# mainboard_rev_b.net
KiCad netlist of a schematic drawn in EAGLE
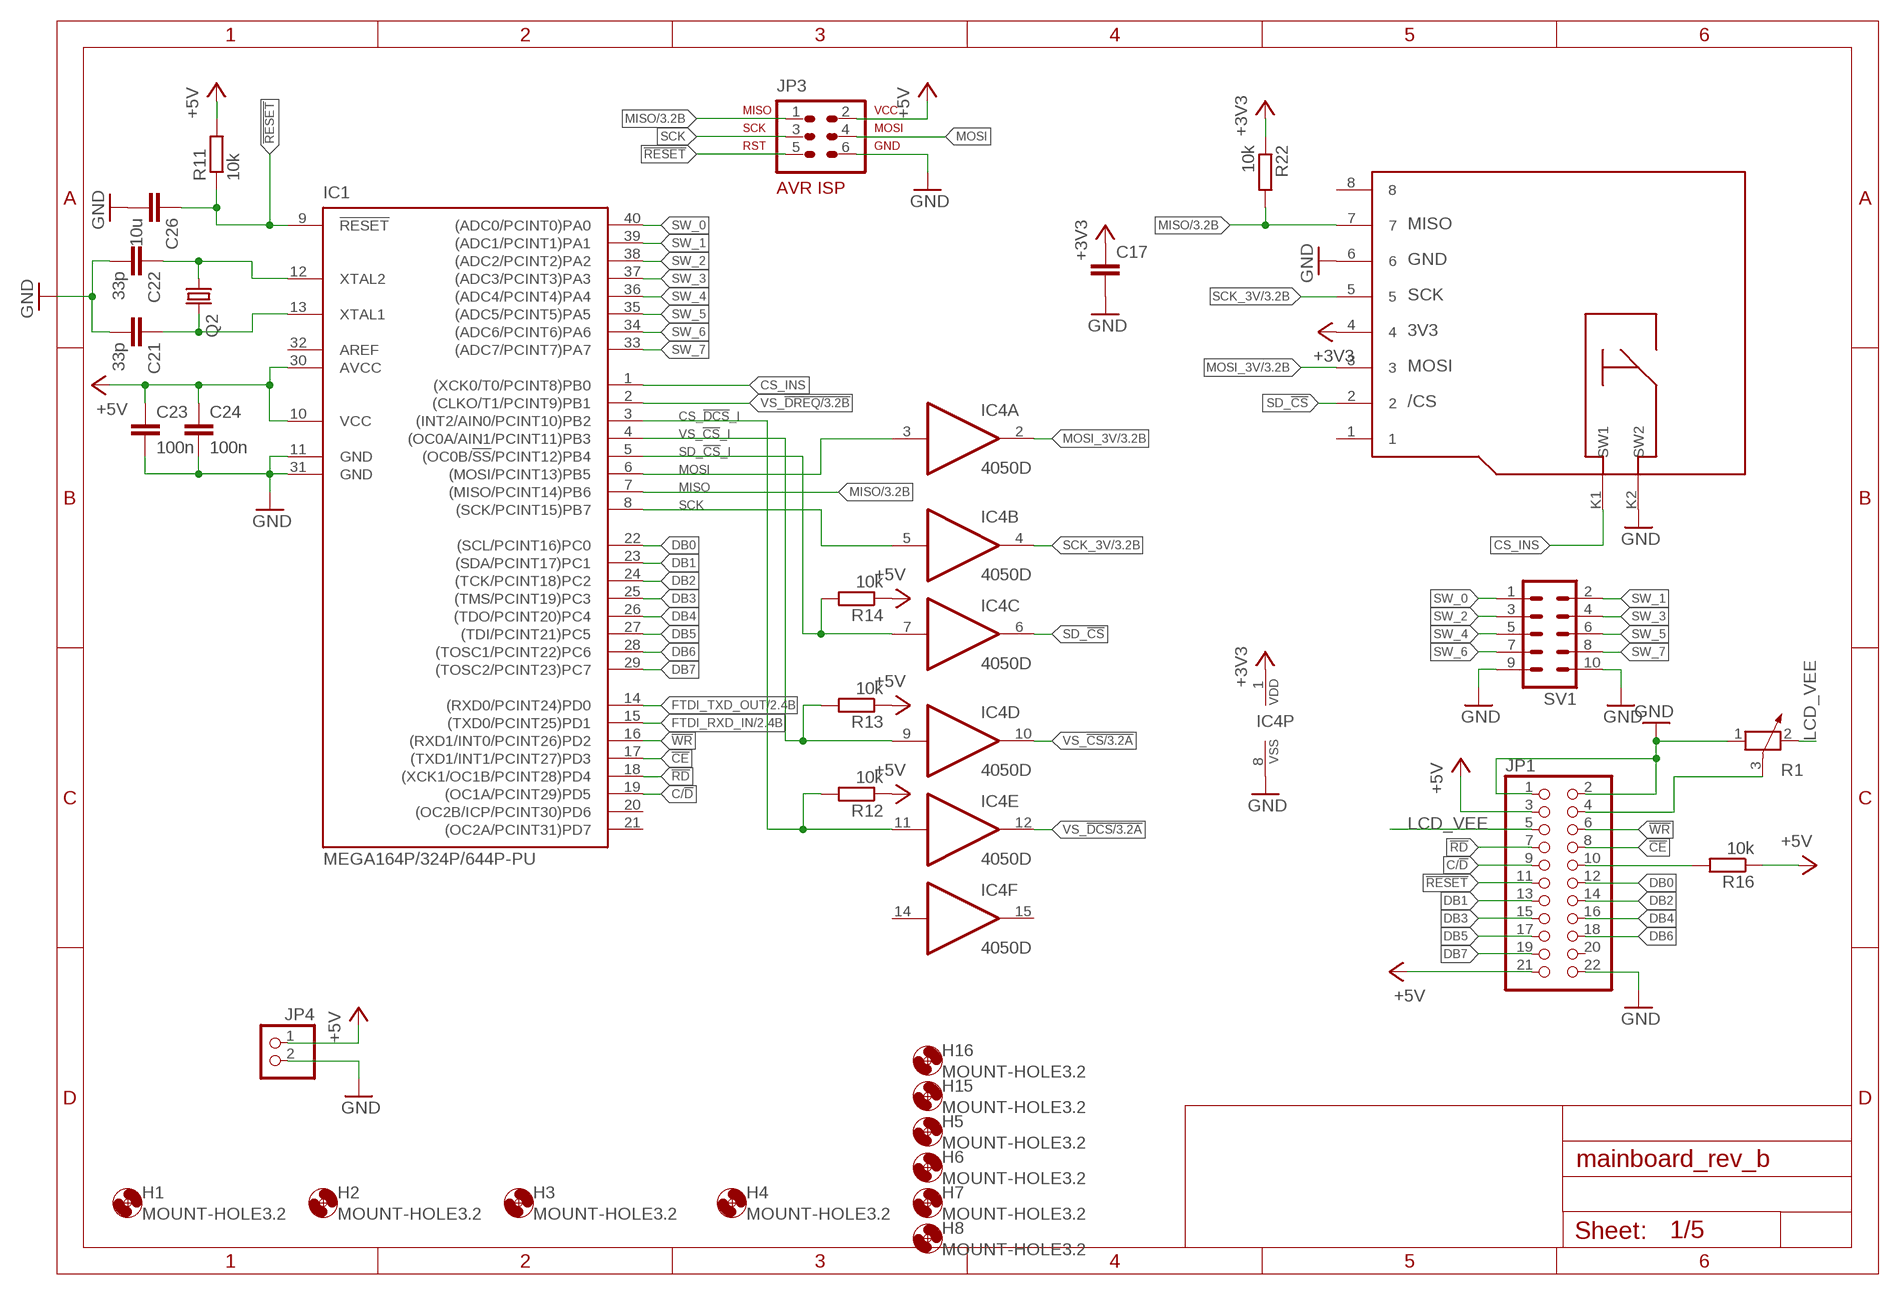
[diagram p0: schematic, sheet 1]
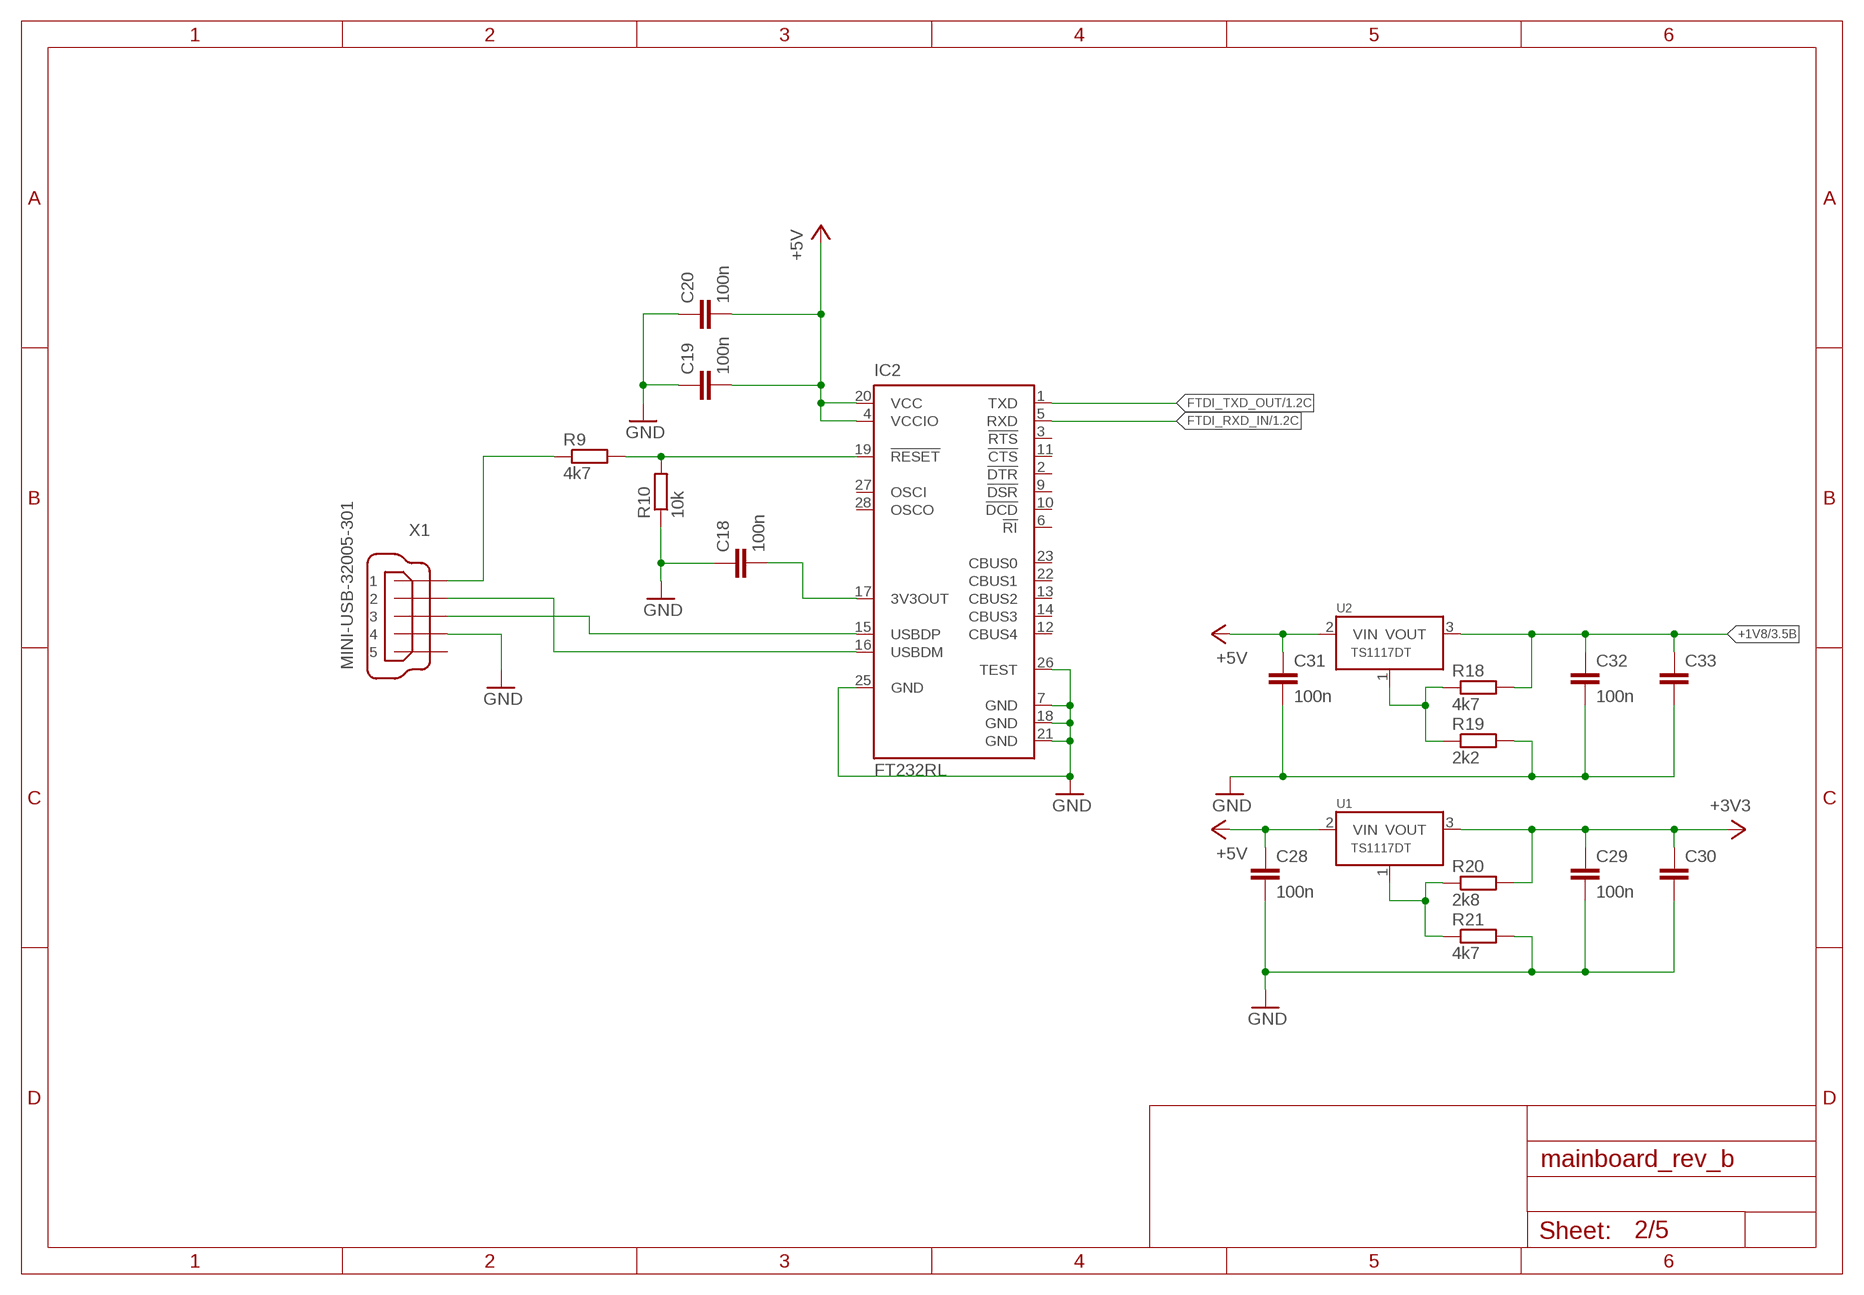
[diagram p1: schematic, sheet 2]
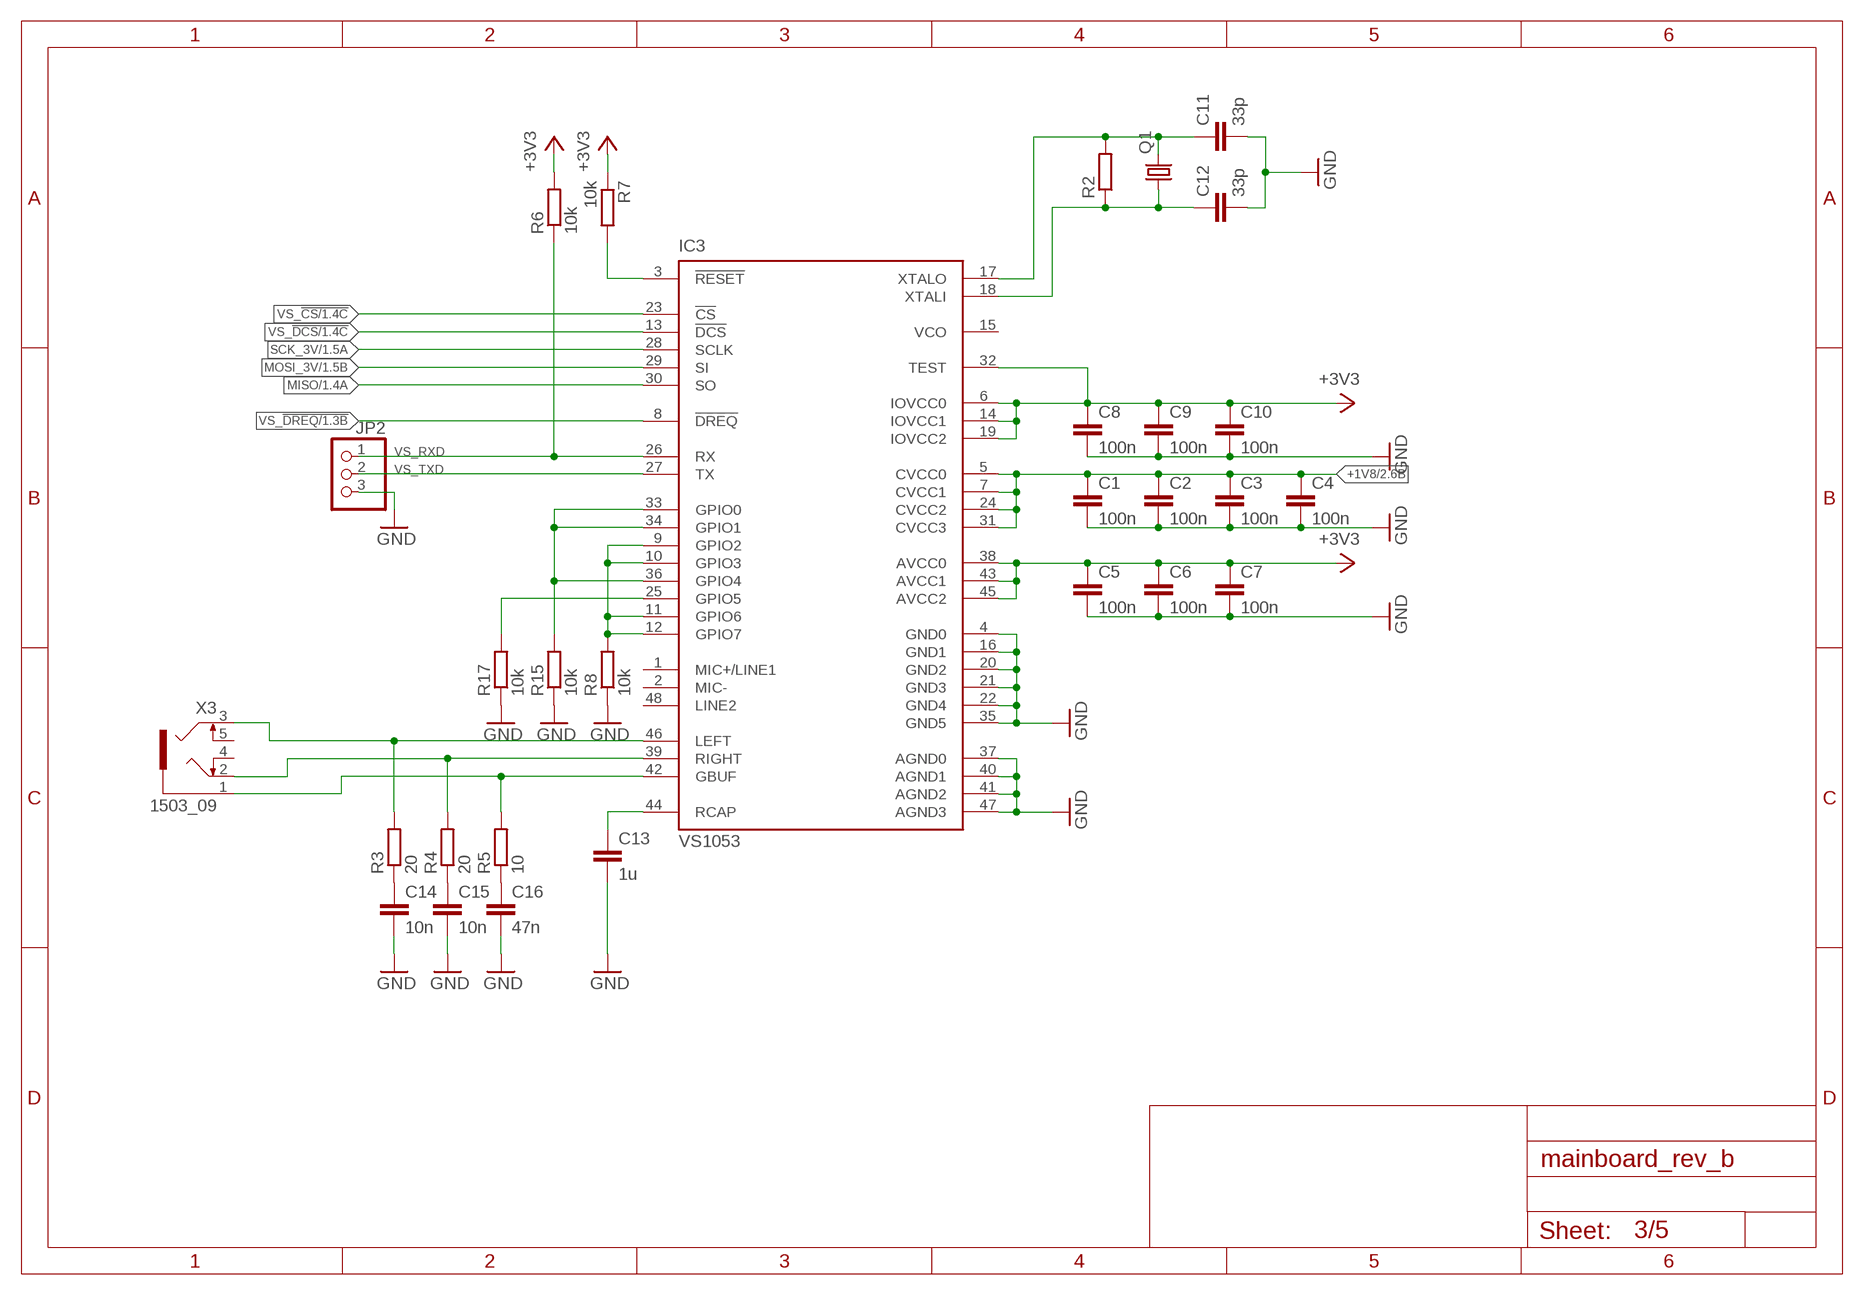
[diagram p2: schematic, sheet 3]
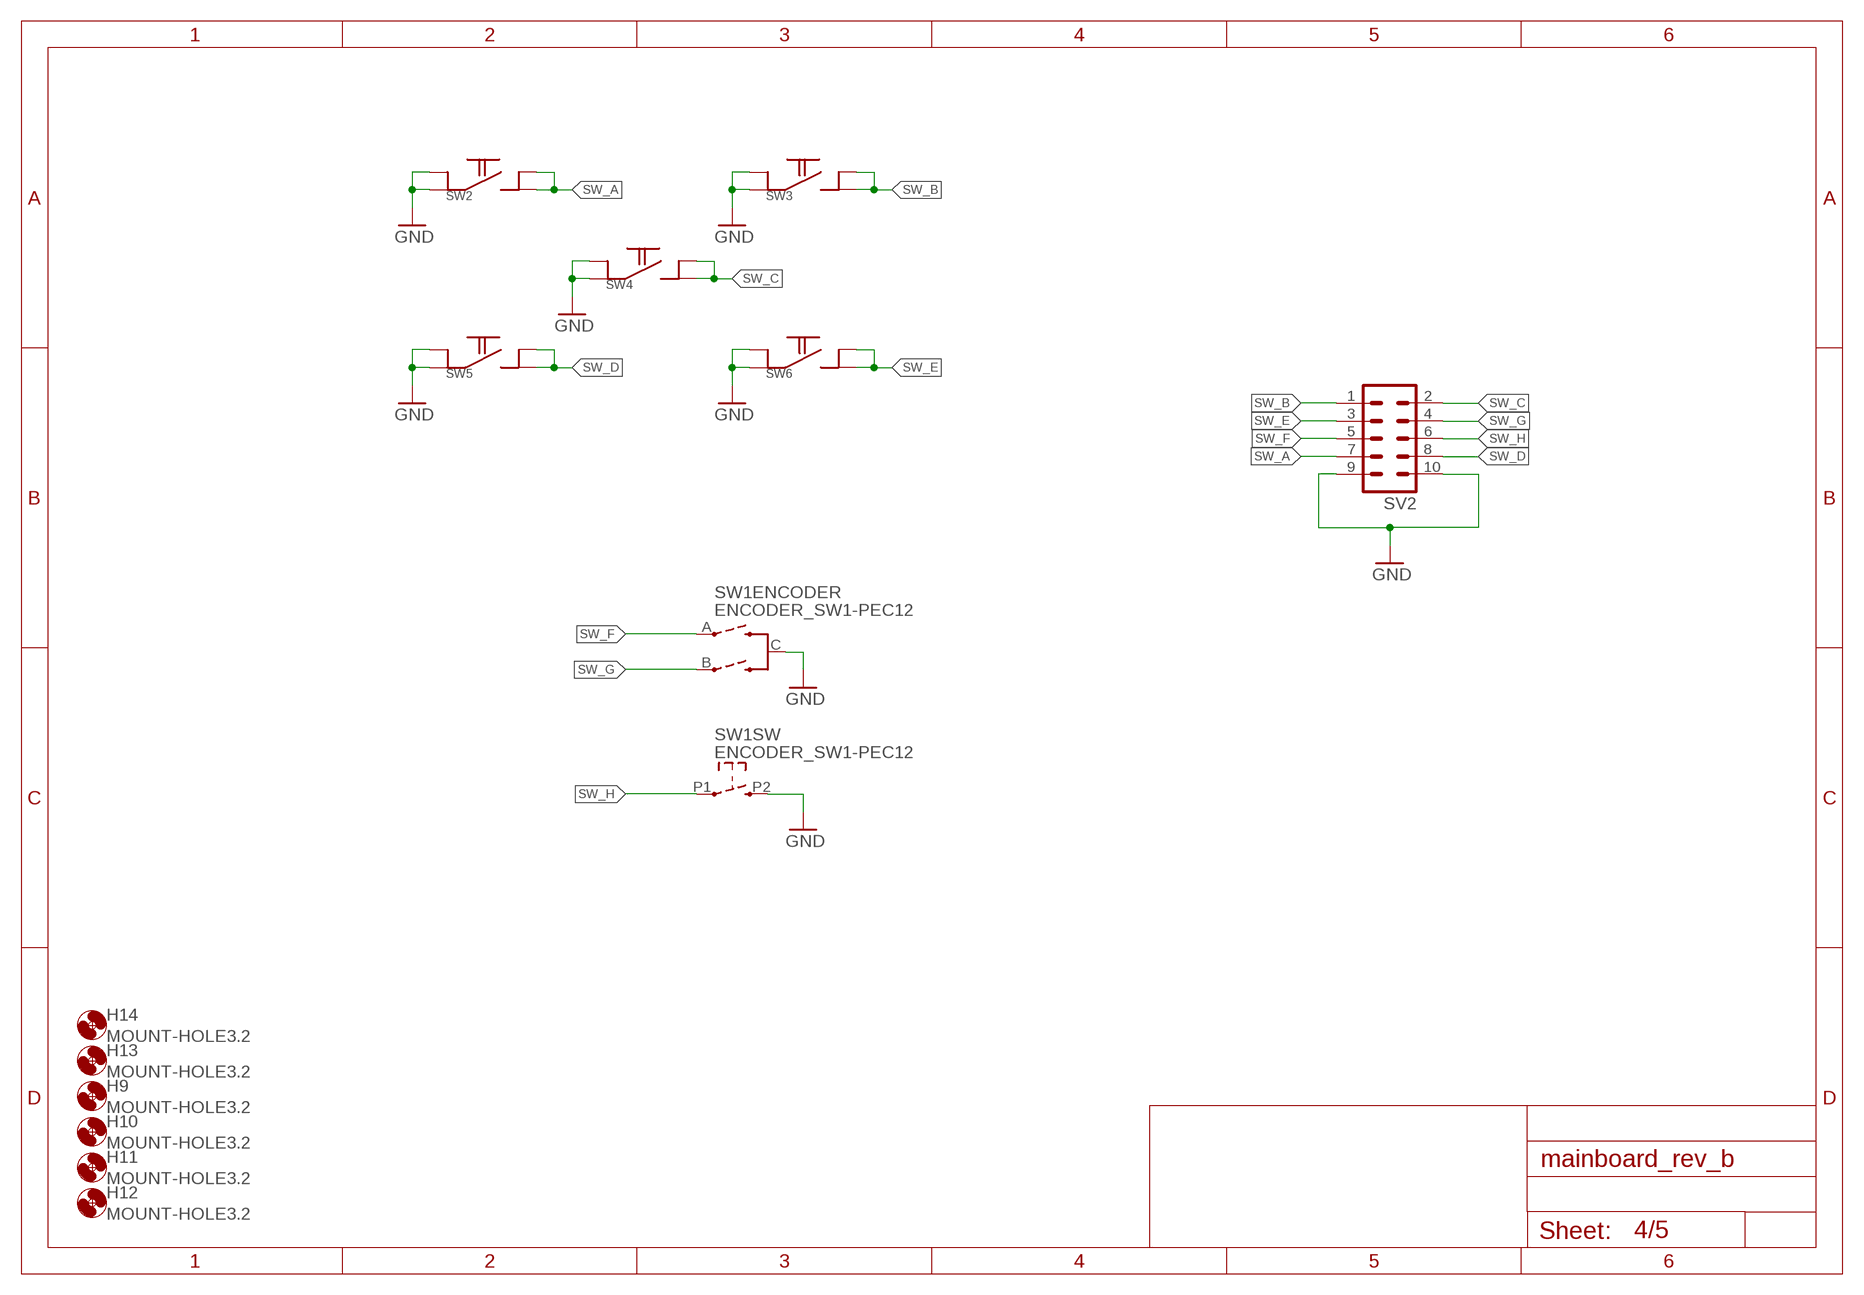
[diagram p3: schematic, sheet 4]
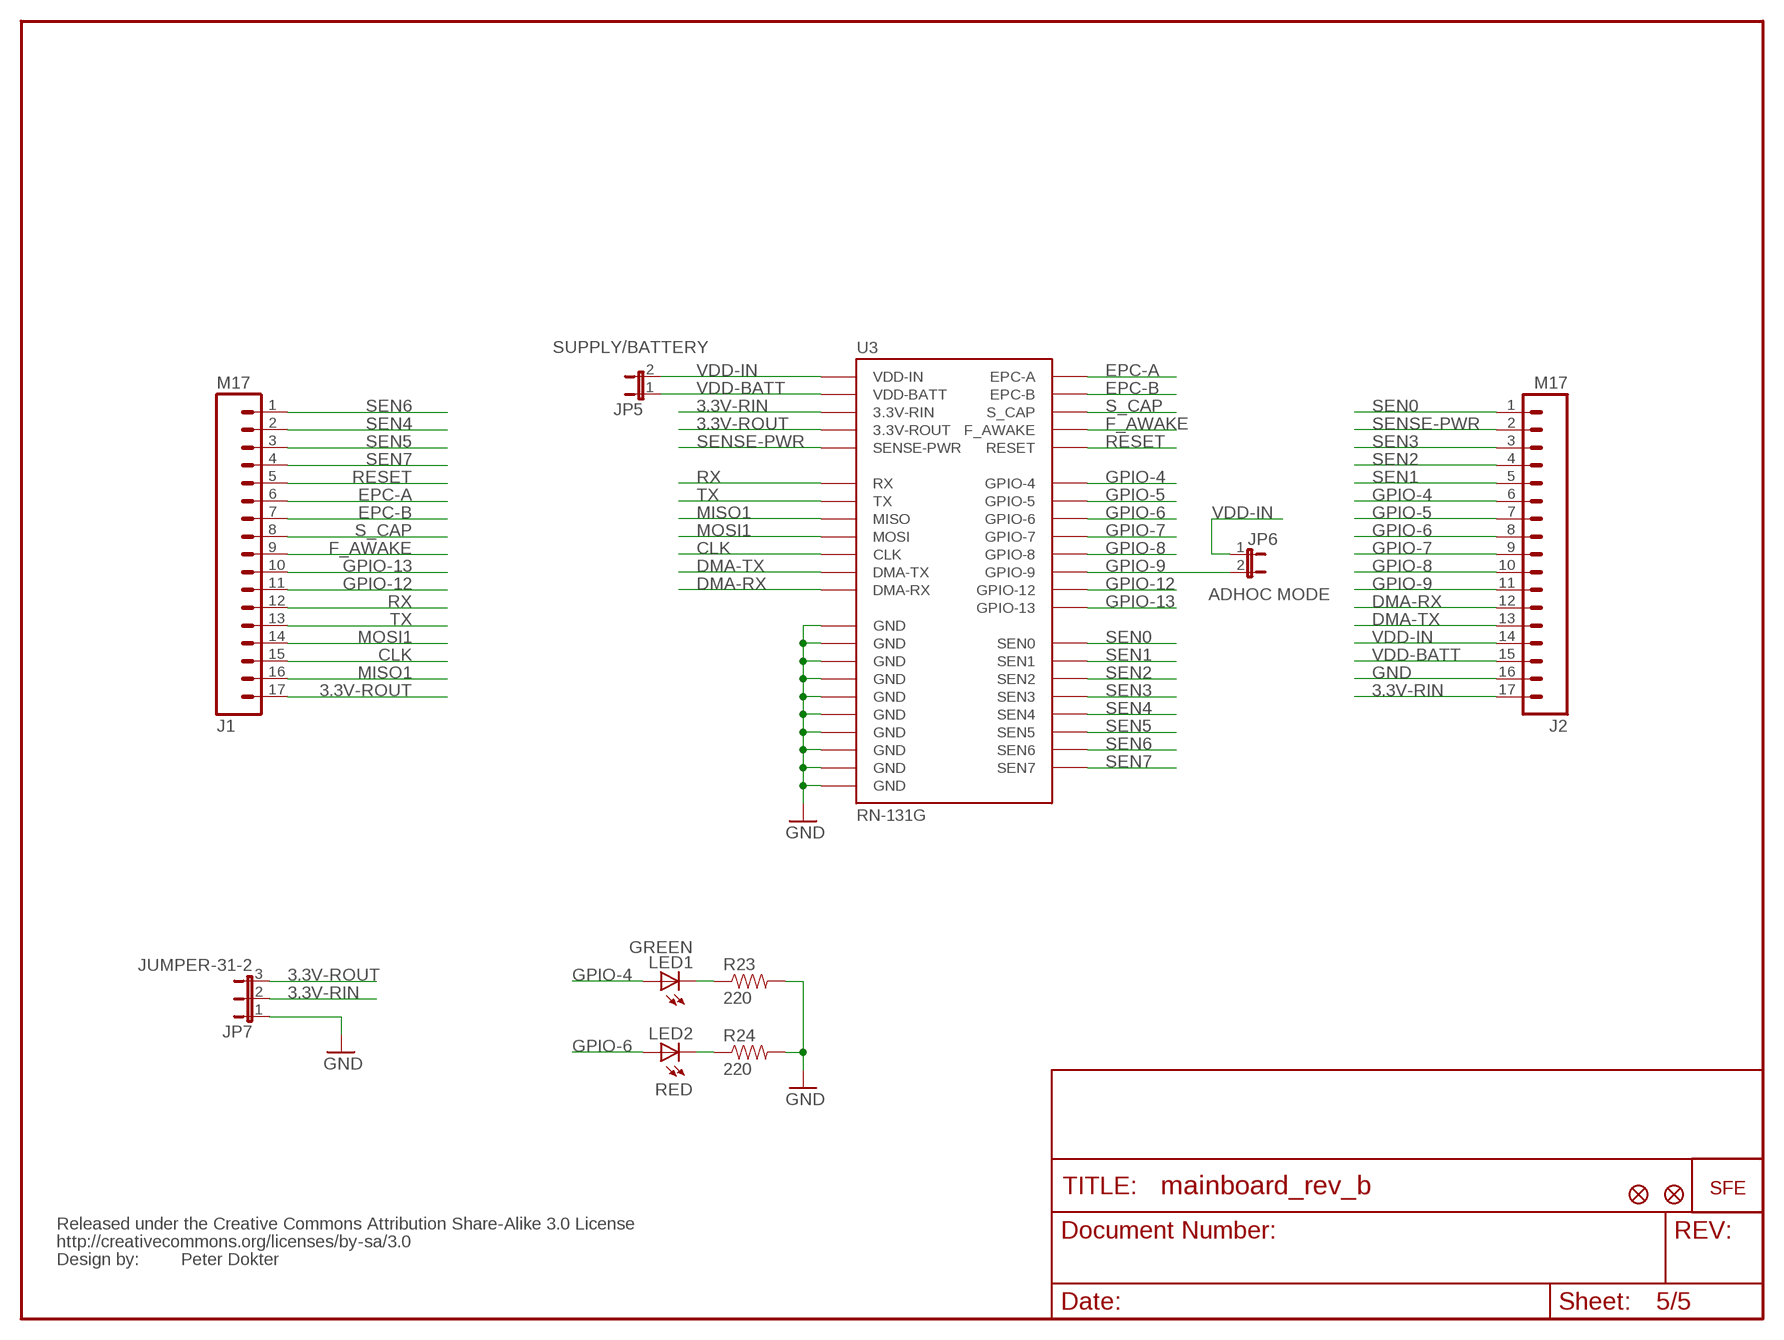
[diagram p4: schematic, sheet 5]

(export (version "E")
  (design (tool "Eeschema 10.0.6"))
  (components
    (comp (ref "H9")
      (value "MOUNT-HOLE3.2")
      (footprint "eagle-import:3,2")
      (libsource (lib "eagle-import") (part "MOUNT-HOLE3.2"))
    )
    (comp (ref "H10")
      (value "MOUNT-HOLE3.2")
      (footprint "eagle-import:3,2")
      (libsource (lib "eagle-import") (part "MOUNT-HOLE3.2"))
    )
    (comp (ref "H11")
      (value "MOUNT-HOLE3.2")
      (footprint "eagle-import:3,2")
      (libsource (lib "eagle-import") (part "MOUNT-HOLE3.2"))
    )
    (comp (ref "H12")
      (value "MOUNT-HOLE3.2")
      (footprint "eagle-import:3,2")
      (libsource (lib "eagle-import") (part "MOUNT-HOLE3.2"))
    )
    (comp (ref "H13")
      (value "MOUNT-HOLE3.2")
      (footprint "eagle-import:3,2")
      (libsource (lib "eagle-import") (part "MOUNT-HOLE3.2"))
    )
    (comp (ref "H14")
      (value "MOUNT-HOLE3.2")
      (footprint "eagle-import:3,2")
      (libsource (lib "eagle-import") (part "MOUNT-HOLE3.2"))
    )
    (comp (ref "SV2")
      (value "ML10")
      (footprint "eagle-import:ML10")
      (libsource (lib "eagle-import") (part "ML10"))
    )
    (comp (ref "SW1")
      (value "ENCODER_SW1-PEC12")
      (footprint "eagle-import:PEC12_INCREMENTAL_ENCODER")
      (libsource (lib "eagle-import") (part "ENCODER_SW1-PEC12"))
    )
    (comp (ref "SW2")
      (value "PUSHBUTTON_12X12")
      (footprint "eagle-import:PUSHBUTTON_12X12")
      (libsource (lib "eagle-import") (part "PUSHBUTTON_12X12"))
    )
    (comp (ref "SW3")
      (value "PUSHBUTTON_12X12")
      (footprint "eagle-import:PUSHBUTTON_12X12")
      (libsource (lib "eagle-import") (part "PUSHBUTTON_12X12"))
    )
    (comp (ref "SW4")
      (value "PUSHBUTTON_12X12")
      (footprint "eagle-import:PUSHBUTTON_12X12")
      (libsource (lib "eagle-import") (part "PUSHBUTTON_12X12"))
    )
    (comp (ref "SW5")
      (value "PUSHBUTTON_12X12")
      (footprint "eagle-import:PUSHBUTTON_12X12")
      (libsource (lib "eagle-import") (part "PUSHBUTTON_12X12"))
    )
    (comp (ref "SW6")
      (value "PUSHBUTTON_12X12")
      (footprint "eagle-import:PUSHBUTTON_12X12")
      (libsource (lib "eagle-import") (part "PUSHBUTTON_12X12"))
    )
    (comp (ref "C1")
      (value "100n")
      (footprint "eagle-import:C0603")
      (libsource (lib "eagle-import") (part "C-EUC0603"))
    )
    (comp (ref "C2")
      (value "100n")
      (footprint "eagle-import:C0603")
      (libsource (lib "eagle-import") (part "C-EUC0603"))
    )
    (comp (ref "C3")
      (value "100n")
      (footprint "eagle-import:C0603")
      (libsource (lib "eagle-import") (part "C-EUC0603"))
    )
    (comp (ref "C4")
      (value "100n")
      (footprint "eagle-import:C0603")
      (libsource (lib "eagle-import") (part "C-EUC0603"))
    )
    (comp (ref "C5")
      (value "100n")
      (footprint "eagle-import:C0603")
      (libsource (lib "eagle-import") (part "C-EUC0603"))
    )
    (comp (ref "C6")
      (value "100n")
      (footprint "eagle-import:C0603")
      (libsource (lib "eagle-import") (part "C-EUC0603"))
    )
    (comp (ref "C7")
      (value "100n")
      (footprint "eagle-import:C0603")
      (libsource (lib "eagle-import") (part "C-EUC0603"))
    )
    (comp (ref "C8")
      (value "100n")
      (footprint "eagle-import:C0603")
      (libsource (lib "eagle-import") (part "C-EUC0603"))
    )
    (comp (ref "C9")
      (value "100n")
      (footprint "eagle-import:C0603")
      (libsource (lib "eagle-import") (part "C-EUC0603"))
    )
    (comp (ref "C10")
      (value "100n")
      (footprint "eagle-import:C0603")
      (libsource (lib "eagle-import") (part "C-EUC0603"))
    )
    (comp (ref "C11")
      (value "33p")
      (footprint "eagle-import:C0603")
      (libsource (lib "eagle-import") (part "C-EUC0603"))
    )
    (comp (ref "C12")
      (value "33p")
      (footprint "eagle-import:C0603")
      (libsource (lib "eagle-import") (part "C-EUC0603"))
    )
    (comp (ref "C13")
      (value "1u")
      (footprint "eagle-import:C0805")
      (libsource (lib "eagle-import") (part "C-EUC0805"))
    )
    (comp (ref "C14")
      (value "10n")
      (footprint "eagle-import:C0603")
      (libsource (lib "eagle-import") (part "C-EUC0603"))
    )
    (comp (ref "C15")
      (value "10n")
      (footprint "eagle-import:C0603")
      (libsource (lib "eagle-import") (part "C-EUC0603"))
    )
    (comp (ref "C16")
      (value "47n")
      (footprint "eagle-import:C0603")
      (libsource (lib "eagle-import") (part "C-EUC0603"))
    )
    (comp (ref "IC3")
      (value "VS1053")
      (footprint "eagle-import:LQFP-48")
      (libsource (lib "eagle-import") (part "VS1053"))
    )
    (comp (ref "JP2")
      (value "PINHD-1X3")
      (footprint "eagle-import:1X03")
      (libsource (lib "eagle-import") (part "PINHD-1X3"))
    )
    (comp (ref "Q1")
      (value "CRYSTALHC49UP")
      (footprint "eagle-import:HC49UP")
      (libsource (lib "eagle-import") (part "CRYSTALHC49UP"))
    )
    (comp (ref "R2")
      (value "R-EU_R0603")
      (footprint "eagle-import:R0603")
      (libsource (lib "eagle-import") (part "R-EU_R0603"))
    )
    (comp (ref "R3")
      (value "20")
      (footprint "eagle-import:R0603")
      (libsource (lib "eagle-import") (part "R-EU_R0603"))
    )
    (comp (ref "R4")
      (value "20")
      (footprint "eagle-import:R0603")
      (libsource (lib "eagle-import") (part "R-EU_R0603"))
    )
    (comp (ref "R5")
      (value "10")
      (footprint "eagle-import:R0603")
      (libsource (lib "eagle-import") (part "R-EU_R0603"))
    )
    (comp (ref "R6")
      (value "10k")
      (footprint "eagle-import:R0603")
      (libsource (lib "eagle-import") (part "R-EU_R0603"))
    )
    (comp (ref "R7")
      (value "10k")
      (footprint "eagle-import:R0603")
      (libsource (lib "eagle-import") (part "R-EU_R0603"))
    )
    (comp (ref "R8")
      (value "10k")
      (footprint "eagle-import:R0603")
      (libsource (lib "eagle-import") (part "R-EU_R0603"))
    )
    (comp (ref "R15")
      (value "10k")
      (footprint "eagle-import:R0603")
      (libsource (lib "eagle-import") (part "R-EU_R0603"))
    )
    (comp (ref "R17")
      (value "10k")
      (footprint "eagle-import:R0603")
      (libsource (lib "eagle-import") (part "R-EU_R0603"))
    )
    (comp (ref "X3")
      (value "1503_09")
      (footprint "eagle-import:1503_09")
      (libsource (lib "eagle-import") (part "1503_09"))
    )
    (comp (ref "J1")
      (value "M17")
      (footprint "eagle-import:1X17")
      (libsource (lib "eagle-import") (part "M17"))
    )
    (comp (ref "J2")
      (value "M17")
      (footprint "eagle-import:1X17")
      (libsource (lib "eagle-import") (part "M17"))
    )
    (comp (ref "JP5")
      (value "JUMPER-2SMD-NO")
      (footprint "eagle-import:SJ_2S-NO")
      (libsource (lib "eagle-import") (part "JUMPER-2SMD-NO"))
    )
    (comp (ref "JP6")
      (value "JUMPER-2SMD-NO")
      (footprint "eagle-import:SJ_2S-NO")
      (libsource (lib "eagle-import") (part "JUMPER-2SMD-NO"))
    )
    (comp (ref "JP7")
      (value "JUMPER-31-2")
      (footprint "eagle-import:SJ_3_PASTE1&2")
      (libsource (lib "eagle-import") (part "JUMPER-31-2"))
    )
    (comp (ref "LED1")
      (value "GREEN")
      (footprint "eagle-import:LED-0603")
      (libsource (lib "eagle-import") (part "LED0603"))
    )
    (comp (ref "LED2")
      (value "RED")
      (footprint "eagle-import:LED-0603")
      (libsource (lib "eagle-import") (part "LED0603"))
    )
    (comp (ref "R23")
      (value "220")
      (footprint "eagle-import:0402-RES")
      (libsource (lib "eagle-import") (part "RESISTOR0402-RES"))
    )
    (comp (ref "R24")
      (value "220")
      (footprint "eagle-import:0402-RES")
      (libsource (lib "eagle-import") (part "RESISTOR0402-RES"))
    )
    (comp (ref "U$1")
      (value "LOGO-SFENEW")
      (footprint "eagle-import:SFE-NEW-WEBLOGO")
      (libsource (lib "eagle-import") (part "LOGO-SFENEW"))
    )
    (comp (ref "U$2")
      (value "FIDUCIAL1X2")
      (footprint "eagle-import:FIDUCIAL-1X2")
      (libsource (lib "eagle-import") (part "FIDUCIAL1X2"))
    )
    (comp (ref "U$3")
      (value "FIDUCIAL1X2")
      (footprint "eagle-import:FIDUCIAL-1X2")
      (libsource (lib "eagle-import") (part "FIDUCIAL1X2"))
    )
    (comp (ref "U$4")
      (value "CREATIVE_COMMONS")
      (footprint "eagle-import:CREATIVE_COMMONS")
      (libsource (lib "eagle-import") (part "CREATIVE_COMMONS"))
    )
    (comp (ref "U3")
      (value "RN-131G")
      (footprint "eagle-import:RN-131G")
      (libsource (lib "eagle-import") (part "RN-131G"))
    )
    (comp (ref "C18")
      (value "100n")
      (footprint "eagle-import:C0603")
      (libsource (lib "eagle-import") (part "C-EUC0603"))
    )
    (comp (ref "C19")
      (value "100n")
      (footprint "eagle-import:C0603")
      (libsource (lib "eagle-import") (part "C-EUC0603"))
    )
    (comp (ref "C20")
      (value "100n")
      (footprint "eagle-import:C0603")
      (libsource (lib "eagle-import") (part "C-EUC0603"))
    )
    (comp (ref "C28")
      (value "100n")
      (footprint "eagle-import:C0603")
      (libsource (lib "eagle-import") (part "C-EUC0603"))
    )
    (comp (ref "C29")
      (value "100n")
      (footprint "eagle-import:C0603")
      (libsource (lib "eagle-import") (part "C-EUC0603"))
    )
    (comp (ref "C30")
      (value "C-EUC1206")
      (footprint "eagle-import:C1206")
      (libsource (lib "eagle-import") (part "C-EUC1206"))
    )
    (comp (ref "C31")
      (value "100n")
      (footprint "eagle-import:C0603")
      (libsource (lib "eagle-import") (part "C-EUC0603"))
    )
    (comp (ref "C32")
      (value "100n")
      (footprint "eagle-import:C0603")
      (libsource (lib "eagle-import") (part "C-EUC0603"))
    )
    (comp (ref "C33")
      (value "C-EUC1206")
      (footprint "eagle-import:C1206")
      (libsource (lib "eagle-import") (part "C-EUC1206"))
    )
    (comp (ref "IC2")
      (value "FT232RL")
      (footprint "eagle-import:SSOP28")
      (libsource (lib "eagle-import") (part "FT232RL"))
    )
    (comp (ref "R9")
      (value "4k7")
      (footprint "eagle-import:R0603")
      (libsource (lib "eagle-import") (part "R-EU_R0603"))
    )
    (comp (ref "R10")
      (value "10k")
      (footprint "eagle-import:R0603")
      (libsource (lib "eagle-import") (part "R-EU_R0603"))
    )
    (comp (ref "R18")
      (value "4k7")
      (footprint "eagle-import:R0603")
      (libsource (lib "eagle-import") (part "R-EU_R0603"))
    )
    (comp (ref "R19")
      (value "2k2")
      (footprint "eagle-import:R0603")
      (libsource (lib "eagle-import") (part "R-EU_R0603"))
    )
    (comp (ref "R20")
      (value "2k8")
      (footprint "eagle-import:R0603")
      (libsource (lib "eagle-import") (part "R-EU_R0603"))
    )
    (comp (ref "R21")
      (value "4k7")
      (footprint "eagle-import:R0603")
      (libsource (lib "eagle-import") (part "R-EU_R0603"))
    )
    (comp (ref "U1")
      (value "TS1117DT")
      (footprint "eagle-import:TO252")
      (libsource (lib "eagle-import") (part "TS1117DT"))
    )
    (comp (ref "U2")
      (value "TS1117DT")
      (footprint "eagle-import:TO252")
      (libsource (lib "eagle-import") (part "TS1117DT"))
    )
    (comp (ref "X1")
      (value "MINI-USB-32005-301")
      (footprint "eagle-import:32005-301")
      (libsource (lib "eagle-import") (part "MINI-USB-32005-301"))
    )
    (comp (ref "C17")
      (value "C-EUC1206")
      (footprint "eagle-import:C1206")
      (libsource (lib "eagle-import") (part "C-EUC1206"))
    )
    (comp (ref "C21")
      (value "33p")
      (footprint "eagle-import:C0603")
      (libsource (lib "eagle-import") (part "C-EUC0603"))
    )
    (comp (ref "C22")
      (value "33p")
      (footprint "eagle-import:C0603")
      (libsource (lib "eagle-import") (part "C-EUC0603"))
    )
    (comp (ref "C23")
      (value "100n")
      (footprint "eagle-import:C0603")
      (libsource (lib "eagle-import") (part "C-EUC0603"))
    )
    (comp (ref "C24")
      (value "100n")
      (footprint "eagle-import:C0603")
      (libsource (lib "eagle-import") (part "C-EUC0603"))
    )
    (comp (ref "C26")
      (value "10u")
      (footprint "eagle-import:C1206")
      (libsource (lib "eagle-import") (part "C-EUC1206"))
    )
    (comp (ref "H1")
      (value "MOUNT-HOLE3.2")
      (footprint "eagle-import:3,2")
      (libsource (lib "eagle-import") (part "MOUNT-HOLE3.2"))
    )
    (comp (ref "H2")
      (value "MOUNT-HOLE3.2")
      (footprint "eagle-import:3,2")
      (libsource (lib "eagle-import") (part "MOUNT-HOLE3.2"))
    )
    (comp (ref "H3")
      (value "MOUNT-HOLE3.2")
      (footprint "eagle-import:3,2")
      (libsource (lib "eagle-import") (part "MOUNT-HOLE3.2"))
    )
    (comp (ref "H4")
      (value "MOUNT-HOLE3.2")
      (footprint "eagle-import:3,2")
      (libsource (lib "eagle-import") (part "MOUNT-HOLE3.2"))
    )
    (comp (ref "H5")
      (value "MOUNT-HOLE3.2")
      (footprint "eagle-import:3,2")
      (libsource (lib "eagle-import") (part "MOUNT-HOLE3.2"))
    )
    (comp (ref "H6")
      (value "MOUNT-HOLE3.2")
      (footprint "eagle-import:3,2")
      (libsource (lib "eagle-import") (part "MOUNT-HOLE3.2"))
    )
    (comp (ref "H7")
      (value "MOUNT-HOLE3.2")
      (footprint "eagle-import:3,2")
      (libsource (lib "eagle-import") (part "MOUNT-HOLE3.2"))
    )
    (comp (ref "H8")
      (value "MOUNT-HOLE3.2")
      (footprint "eagle-import:3,2")
      (libsource (lib "eagle-import") (part "MOUNT-HOLE3.2"))
    )
    (comp (ref "H15")
      (value "MOUNT-HOLE3.2")
      (footprint "eagle-import:3,2")
      (libsource (lib "eagle-import") (part "MOUNT-HOLE3.2"))
    )
    (comp (ref "H16")
      (value "MOUNT-HOLE3.2")
      (footprint "eagle-import:3,2")
      (libsource (lib "eagle-import") (part "MOUNT-HOLE3.2"))
    )
    (comp (ref "IC1")
      (value "MEGA164P/324P/644P-PU")
      (footprint "eagle-import:DIL40")
      (libsource (lib "eagle-import") (part "MEGA164P/324P/644P-PU"))
    )
    (comp (ref "IC4")
      (value "4050D")
      (footprint "eagle-import:SO16")
      (libsource (lib "eagle-import") (part "4050D"))
    )
    (comp (ref "JP1")
      (value "PINHD-2X11")
      (footprint "eagle-import:2X11")
      (libsource (lib "eagle-import") (part "PINHD-2X11"))
    )
    (comp (ref "JP3")
      (value "AVR-ISP-6VERT")
      (footprint "eagle-import:AVR-ISP-6")
      (libsource (lib "eagle-import") (part "AVR-ISP-6VERT"))
    )
    (comp (ref "JP4")
      (value "PINHD-1X2")
      (footprint "eagle-import:1X02")
      (libsource (lib "eagle-import") (part "PINHD-1X2"))
    )
    (comp (ref "Q2")
      (value "CRYSTALHC49UP")
      (footprint "eagle-import:HC49UP")
      (libsource (lib "eagle-import") (part "CRYSTALHC49UP"))
    )
    (comp (ref "R1")
      (value "POTENTIOMETER_PT_SPIN")
      (footprint "eagle-import:PT-SPIN")
      (libsource (lib "eagle-import") (part "POTENTIOMETER_PT_SPIN"))
    )
    (comp (ref "R11")
      (value "10k")
      (footprint "eagle-import:R0603")
      (libsource (lib "eagle-import") (part "R-EU_R0603"))
    )
    (comp (ref "R12")
      (value "10k")
      (footprint "eagle-import:R0603")
      (libsource (lib "eagle-import") (part "R-EU_R0603"))
    )
    (comp (ref "R13")
      (value "10k")
      (footprint "eagle-import:R0603")
      (libsource (lib "eagle-import") (part "R-EU_R0603"))
    )
    (comp (ref "R14")
      (value "10k")
      (footprint "eagle-import:R0603")
      (libsource (lib "eagle-import") (part "R-EU_R0603"))
    )
    (comp (ref "R16")
      (value "10k")
      (footprint "eagle-import:R0603")
      (libsource (lib "eagle-import") (part "R-EU_R0603"))
    )
    (comp (ref "R22")
      (value "10k")
      (footprint "eagle-import:R0603")
      (libsource (lib "eagle-import") (part "R-EU_R0603"))
    )
    (comp (ref "SV1")
      (value "ML10")
      (footprint "eagle-import:ML10")
      (libsource (lib "eagle-import") (part "ML10"))
    )
    (comp (ref "X2")
      (value "MICRO-SD")
      (footprint "eagle-import:MICRO-SD")
      (libsource (lib "eagle-import") (part "MICRO-SD"))
    )
  )
  (nets
    (net (code "1") (name "+1V8") (class "Default")
      (node (ref "C1") (pin "1") (pinfunction "1_1") (pintype "passive"))
      (node (ref "C2") (pin "1") (pinfunction "1_1") (pintype "passive"))
      (node (ref "C3") (pin "1") (pinfunction "1_1") (pintype "passive"))
      (node (ref "C32") (pin "1") (pinfunction "1_1") (pintype "passive"))
      (node (ref "C33") (pin "1") (pinfunction "1_1") (pintype "passive"))
      (node (ref "C4") (pin "1") (pinfunction "1_1") (pintype "passive"))
      (node (ref "IC3") (pin "24") (pinfunction "CVCC2_24") (pintype "power_in"))
      (node (ref "IC3") (pin "31") (pinfunction "CVCC3_31") (pintype "power_in"))
      (node (ref "IC3") (pin "5") (pinfunction "CVCC0_5") (pintype "power_in"))
      (node (ref "IC3") (pin "7") (pinfunction "CVCC1_7") (pintype "power_in"))
      (node (ref "R18") (pin "2") (pinfunction "2_2") (pintype "passive"))
      (node (ref "U2") (pin "3") (pinfunction "VOUT_3") (pintype "power_in"))
    )
    (net (code "2") (name "+3V3") (class "Default")
      (node (ref "C10") (pin "1") (pinfunction "1_1") (pintype "passive"))
      (node (ref "C17") (pin "1") (pinfunction "1_1") (pintype "passive"))
      (node (ref "C29") (pin "1") (pinfunction "1_1") (pintype "passive"))
      (node (ref "C30") (pin "1") (pinfunction "1_1") (pintype "passive"))
      (node (ref "C5") (pin "1") (pinfunction "1_1") (pintype "passive"))
      (node (ref "C6") (pin "1") (pinfunction "1_1") (pintype "passive"))
      (node (ref "C7") (pin "1") (pinfunction "1_1") (pintype "passive"))
      (node (ref "C8") (pin "1") (pinfunction "1_1") (pintype "passive"))
      (node (ref "C9") (pin "1") (pinfunction "1_1") (pintype "passive"))
      (node (ref "IC3") (pin "14") (pinfunction "IOVCC1_14") (pintype "power_in"))
      (node (ref "IC3") (pin "19") (pinfunction "IOVCC2_19") (pintype "power_in"))
      (node (ref "IC3") (pin "32") (pinfunction "TEST_32") (pintype "input"))
      (node (ref "IC3") (pin "38") (pinfunction "AVCC0_38") (pintype "power_in"))
      (node (ref "IC3") (pin "43") (pinfunction "AVCC1_43") (pintype "power_in"))
      (node (ref "IC3") (pin "45") (pinfunction "AVCC2_45") (pintype "power_in"))
      (node (ref "IC3") (pin "6") (pinfunction "IOVCC0_6") (pintype "power_in"))
      (node (ref "IC4") (pin "1") (pinfunction "VDD_1") (pintype "power_in"))
      (node (ref "R20") (pin "2") (pinfunction "2_2") (pintype "passive"))
      (node (ref "R22") (pin "1") (pinfunction "1_1") (pintype "passive"))
      (node (ref "R6") (pin "2") (pinfunction "2_2") (pintype "passive"))
      (node (ref "R7") (pin "1") (pinfunction "1_1") (pintype "passive"))
      (node (ref "U1") (pin "3") (pinfunction "VOUT_3") (pintype "power_in"))
      (node (ref "X2") (pin "4") (pinfunction "4_4") (pintype "bidirectional"))
    )
    (net (code "3") (name "+5V") (class "Default")
      (node (ref "C19") (pin "2") (pinfunction "2_2") (pintype "passive"))
      (node (ref "C20") (pin "2") (pinfunction "2_2") (pintype "passive"))
      (node (ref "C23") (pin "1") (pinfunction "1_1") (pintype "passive"))
      (node (ref "C24") (pin "1") (pinfunction "1_1") (pintype "passive"))
      (node (ref "C28") (pin "1") (pinfunction "1_1") (pintype "passive"))
      (node (ref "C31") (pin "1") (pinfunction "1_1") (pintype "passive"))
      (node (ref "IC1") (pin "10") (pinfunction "VCC_10") (pintype "power_in"))
      (node (ref "IC1") (pin "30") (pinfunction "AVCC_30") (pintype "power_in"))
      (node (ref "IC2") (pin "20") (pinfunction "VCC_20") (pintype "power_in"))
      (node (ref "IC2") (pin "4") (pinfunction "VCCIO_4") (pintype "power_in"))
      (node (ref "JP1") (pin "21") (pinfunction "21_21") (pintype "passive"))
      (node (ref "JP1") (pin "3") (pinfunction "3_3") (pintype "passive"))
      (node (ref "JP3") (pin "2") (pinfunction "2_2") (pintype "passive"))
      (node (ref "JP4") (pin "1") (pinfunction "1_1") (pintype "passive"))
      (node (ref "R11") (pin "2") (pinfunction "2_2") (pintype "passive"))
      (node (ref "R12") (pin "1") (pinfunction "1_1") (pintype "passive"))
      (node (ref "R13") (pin "1") (pinfunction "1_1") (pintype "passive"))
      (node (ref "R14") (pin "1") (pinfunction "1_1") (pintype "passive"))
      (node (ref "R16") (pin "1") (pinfunction "1_1") (pintype "passive"))
      (node (ref "U1") (pin "2") (pinfunction "VIN_2") (pintype "power_in"))
      (node (ref "U2") (pin "2") (pinfunction "VIN_2") (pintype "power_in"))
    )
    (net (code "4") (name "3.3V-RIN") (class "Default")
      (node (ref "J2") (pin "17") (pinfunction "17_17") (pintype "passive"))
      (node (ref "JP7") (pin "2") (pinfunction "2_2") (pintype "passive"))
      (node (ref "U3") (pin "P$18") (pinfunction "3.3V-RIN_P$18") (pintype "bidirectional"))
    )
    (net (code "5") (name "3.3V-ROUT") (class "Default")
      (node (ref "J1") (pin "17") (pinfunction "17_17") (pintype "passive"))
      (node (ref "JP7") (pin "3") (pinfunction "3_3") (pintype "passive"))
      (node (ref "U3") (pin "P$17") (pinfunction "3.3V-ROUT_P$17") (pintype "bidirectional"))
    )
    (net (code "6") (name "AREF") (class "Default")
      (node (ref "IC1") (pin "32") (pinfunction "AREF_32") (pintype "power_in"))
    )
    (net (code "7") (name "CLK") (class "Default")
      (node (ref "J1") (pin "15") (pinfunction "15_15") (pintype "passive"))
      (node (ref "U3") (pin "P$15") (pinfunction "CLK_P$15") (pintype "bidirectional"))
    )
    (net (code "8") (name "CS_INS") (class "Default")
      (node (ref "IC1") (pin "1") (pinfunction "(XCK0/T0/PCINT8)PB0_1") (pintype "bidirectional"))
      (node (ref "X2") (pin "K1") (pinfunction "SW1_K1") (pintype "bidirectional"))
    )
    (net (code "9") (name "CS_~{DCS}_I") (class "Default")
      (node (ref "IC1") (pin "3") (pinfunction "(INT2/AIN0/PCINT10)PB2_3") (pintype "bidirectional"))
      (node (ref "IC4") (pin "11") (pinfunction "I_11") (pintype "input"))
      (node (ref "R12") (pin "2") (pinfunction "2_2") (pintype "passive"))
    )
    (net (code "10") (name "C{slash}~{D}") (class "Default")
      (node (ref "IC1") (pin "19") (pinfunction "(OC1A/PCINT29)PD5_19") (pintype "bidirectional"))
      (node (ref "JP1") (pin "9") (pinfunction "9_9") (pintype "passive"))
    )
    (net (code "11") (name "DB0") (class "Default")
      (node (ref "IC1") (pin "22") (pinfunction "(SCL/PCINT16)PC0_22") (pintype "bidirectional"))
      (node (ref "JP1") (pin "12") (pinfunction "12_12") (pintype "passive"))
    )
    (net (code "12") (name "DB1") (class "Default")
      (node (ref "IC1") (pin "23") (pinfunction "(SDA/PCINT17)PC1_23") (pintype "bidirectional"))
      (node (ref "JP1") (pin "13") (pinfunction "13_13") (pintype "passive"))
    )
    (net (code "13") (name "DB2") (class "Default")
      (node (ref "IC1") (pin "24") (pinfunction "(TCK/PCINT18)PC2_24") (pintype "bidirectional"))
      (node (ref "JP1") (pin "14") (pinfunction "14_14") (pintype "passive"))
    )
    (net (code "14") (name "DB3") (class "Default")
      (node (ref "IC1") (pin "25") (pinfunction "(TMS/PCINT19)PC3_25") (pintype "bidirectional"))
      (node (ref "JP1") (pin "15") (pinfunction "15_15") (pintype "passive"))
    )
    (net (code "15") (name "DB4") (class "Default")
      (node (ref "IC1") (pin "26") (pinfunction "(TDO/PCINT20)PC4_26") (pintype "bidirectional"))
      (node (ref "JP1") (pin "16") (pinfunction "16_16") (pintype "passive"))
    )
    (net (code "16") (name "DB5") (class "Default")
      (node (ref "IC1") (pin "27") (pinfunction "(TDI/PCINT21)PC5_27") (pintype "bidirectional"))
      (node (ref "JP1") (pin "17") (pinfunction "17_17") (pintype "passive"))
    )
    (net (code "17") (name "DB6") (class "Default")
      (node (ref "IC1") (pin "28") (pinfunction "(TOSC1/PCINT22)PC6_28") (pintype "bidirectional"))
      (node (ref "JP1") (pin "18") (pinfunction "18_18") (pintype "passive"))
    )
    (net (code "18") (name "DB7") (class "Default")
      (node (ref "IC1") (pin "29") (pinfunction "(TOSC2/PCINT23)PC7_29") (pintype "bidirectional"))
      (node (ref "JP1") (pin "19") (pinfunction "19_19") (pintype "passive"))
    )
    (net (code "19") (name "DMA-RX") (class "Default")
      (node (ref "J2") (pin "12") (pinfunction "12_12") (pintype "passive"))
      (node (ref "U3") (pin "P$23") (pinfunction "DMA-RX_P$23") (pintype "bidirectional"))
    )
    (net (code "20") (name "DMA-TX") (class "Default")
      (node (ref "J2") (pin "13") (pinfunction "13_13") (pintype "passive"))
      (node (ref "U3") (pin "P$22") (pinfunction "DMA-TX_P$22") (pintype "bidirectional"))
    )
    (net (code "21") (name "EPC-A") (class "Default")
      (node (ref "J1") (pin "6") (pinfunction "6_6") (pintype "passive"))
      (node (ref "U3") (pin "P$6") (pinfunction "EPC-A_P$6") (pintype "bidirectional"))
    )
    (net (code "22") (name "EPC-B") (class "Default")
      (node (ref "J1") (pin "7") (pinfunction "7_7") (pintype "passive"))
      (node (ref "U3") (pin "P$7") (pinfunction "EPC-B_P$7") (pintype "bidirectional"))
    )
    (net (code "23") (name "FTDI_RXD_IN") (class "Default")
      (node (ref "IC1") (pin "15") (pinfunction "(TXD0/PCINT25)PD1_15") (pintype "bidirectional"))
      (node (ref "IC2") (pin "5") (pinfunction "RXD_5") (pintype "input"))
    )
    (net (code "24") (name "FTDI_TXD_OUT") (class "Default")
      (node (ref "IC1") (pin "14") (pinfunction "(RXD0/PCINT24)PD0_14") (pintype "bidirectional"))
      (node (ref "IC2") (pin "1") (pinfunction "TXD_1") (pintype "output"))
    )
    (net (code "25") (name "F_AWAKE") (class "Default")
      (node (ref "J1") (pin "9") (pinfunction "9_9") (pintype "passive"))
      (node (ref "U3") (pin "P$9") (pinfunction "F_AWAKE_P$9") (pintype "bidirectional"))
    )
    (net (code "26") (name "GND") (class "Default")
      (node (ref "C1") (pin "2") (pinfunction "2_2") (pintype "passive"))
      (node (ref "C10") (pin "2") (pinfunction "2_2") (pintype "passive"))
      (node (ref "C11") (pin "2") (pinfunction "2_2") (pintype "passive"))
      (node (ref "C12") (pin "2") (pinfunction "2_2") (pintype "passive"))
      (node (ref "C13") (pin "2") (pinfunction "2_2") (pintype "passive"))
      (node (ref "C14") (pin "2") (pinfunction "2_2") (pintype "passive"))
      (node (ref "C15") (pin "2") (pinfunction "2_2") (pintype "passive"))
      (node (ref "C16") (pin "2") (pinfunction "2_2") (pintype "passive"))
      (node (ref "C17") (pin "2") (pinfunction "2_2") (pintype "passive"))
      (node (ref "C18") (pin "1") (pinfunction "1_1") (pintype "passive"))
      (node (ref "C19") (pin "1") (pinfunction "1_1") (pintype "passive"))
      (node (ref "C2") (pin "2") (pinfunction "2_2") (pintype "passive"))
      (node (ref "C20") (pin "1") (pinfunction "1_1") (pintype "passive"))
      (node (ref "C21") (pin "2") (pinfunction "2_2") (pintype "passive"))
      (node (ref "C22") (pin "2") (pinfunction "2_2") (pintype "passive"))
      (node (ref "C23") (pin "2") (pinfunction "2_2") (pintype "passive"))
      (node (ref "C24") (pin "2") (pinfunction "2_2") (pintype "passive"))
      (node (ref "C26") (pin "2") (pinfunction "2_2") (pintype "passive"))
      (node (ref "C28") (pin "2") (pinfunction "2_2") (pintype "passive"))
      (node (ref "C29") (pin "2") (pinfunction "2_2") (pintype "passive"))
      (node (ref "C3") (pin "2") (pinfunction "2_2") (pintype "passive"))
      (node (ref "C30") (pin "2") (pinfunction "2_2") (pintype "passive"))
      (node (ref "C31") (pin "2") (pinfunction "2_2") (pintype "passive"))
      (node (ref "C32") (pin "2") (pinfunction "2_2") (pintype "passive"))
      (node (ref "C33") (pin "2") (pinfunction "2_2") (pintype "passive"))
      (node (ref "C4") (pin "2") (pinfunction "2_2") (pintype "passive"))
      (node (ref "C5") (pin "2") (pinfunction "2_2") (pintype "passive"))
      (node (ref "C6") (pin "2") (pinfunction "2_2") (pintype "passive"))
      (node (ref "C7") (pin "2") (pinfunction "2_2") (pintype "passive"))
      (node (ref "C8") (pin "2") (pinfunction "2_2") (pintype "passive"))
      (node (ref "C9") (pin "2") (pinfunction "2_2") (pintype "passive"))
      (node (ref "IC1") (pin "11") (pinfunction "GND_11") (pintype "power_in"))
      (node (ref "IC1") (pin "31") (pinfunction "GND_31") (pintype "power_in"))
      (node (ref "IC2") (pin "18") (pinfunction "GND_18") (pintype "power_in"))
      (node (ref "IC2") (pin "21") (pinfunction "GND_21") (pintype "power_in"))
      (node (ref "IC2") (pin "25") (pinfunction "GND_25") (pintype "power_in"))
      (node (ref "IC2") (pin "26") (pinfunction "TEST_26") (pintype "input"))
      (node (ref "IC2") (pin "7") (pinfunction "GND_7") (pintype "power_in"))
      (node (ref "IC3") (pin "16") (pinfunction "GND1_16") (pintype "power_in"))
      (node (ref "IC3") (pin "20") (pinfunction "GND2_20") (pintype "power_in"))
      (node (ref "IC3") (pin "21") (pinfunction "GND3_21") (pintype "power_in"))
      (node (ref "IC3") (pin "22") (pinfunction "GND4_22") (pintype "power_in"))
      (node (ref "IC3") (pin "35") (pinfunction "GND5_35") (pintype "power_in"))
      (node (ref "IC3") (pin "37") (pinfunction "AGND0_37") (pintype "power_in"))
      (node (ref "IC3") (pin "4") (pinfunction "GND0_4") (pintype "power_in"))
      (node (ref "IC3") (pin "40") (pinfunction "AGND1_40") (pintype "power_in"))
      (node (ref "IC3") (pin "41") (pinfunction "AGND2_41") (pintype "power_in"))
      (node (ref "IC3") (pin "47") (pinfunction "AGND3_47") (pintype "power_in"))
      (node (ref "IC4") (pin "8") (pinfunction "VSS_8") (pintype "power_in"))
      (node (ref "J2") (pin "16") (pinfunction "16_16") (pintype "passive"))
      (node (ref "JP1") (pin "1") (pinfunction "1_1") (pintype "passive"))
      (node (ref "JP1") (pin "2") (pinfunction "2_2") (pintype "passive"))
      (node (ref "JP1") (pin "22") (pinfunction "22_22") (pintype "passive"))
      (node (ref "JP2") (pin "3") (pinfunction "3_3") (pintype "passive"))
      (node (ref "JP3") (pin "6") (pinfunction "6_6") (pintype "passive"))
      (node (ref "JP4") (pin "2") (pinfunction "2_2") (pintype "passive"))
      (node (ref "JP7") (pin "1") (pinfunction "1_1") (pintype "passive"))
      (node (ref "R1") (pin "1") (pinfunction "1_1") (pintype "passive"))
      (node (ref "R10") (pin "1") (pinfunction "1_1") (pintype "passive"))
      (node (ref "R15") (pin "1") (pinfunction "1_1") (pintype "passive"))
      (node (ref "R17") (pin "1") (pinfunction "1_1") (pintype "passive"))
      (node (ref "R19") (pin "2") (pinfunction "2_2") (pintype "passive"))
      (node (ref "R21") (pin "2") (pinfunction "2_2") (pintype "passive"))
      (node (ref "R23") (pin "2") (pinfunction "2_2") (pintype "passive"))
      (node (ref "R24") (pin "2") (pinfunction "2_2") (pintype "passive"))
      (node (ref "R8") (pin "1") (pinfunction "1_1") (pintype "passive"))
      (node (ref "SV1") (pin "10") (pinfunction "10_10") (pintype "passive"))
      (node (ref "SV1") (pin "9") (pinfunction "9_9") (pintype "passive"))
      (node (ref "SV2") (pin "10") (pinfunction "10_10") (pintype "passive"))
      (node (ref "SV2") (pin "9") (pinfunction "9_9") (pintype "passive"))
      (node (ref "SW1") (pin "C") (pinfunction "C_C") (pintype "passive"))
      (node (ref "SW1") (pin "P2") (pinfunction "2_P2") (pintype "passive"))
      (node (ref "SW2") (pin "A@1") (pinfunction "A_A@1") (pintype "passive"))
      (node (ref "SW2") (pin "A@2") (pinfunction "A_A@2") (pintype "passive"))
      (node (ref "SW3") (pin "A@1") (pinfunction "A_A@1") (pintype "passive"))
      (node (ref "SW3") (pin "A@2") (pinfunction "A_A@2") (pintype "passive"))
      (node (ref "SW4") (pin "A@1") (pinfunction "A_A@1") (pintype "passive"))
      (node (ref "SW4") (pin "A@2") (pinfunction "A_A@2") (pintype "passive"))
      (node (ref "SW5") (pin "A@1") (pinfunction "A_A@1") (pintype "passive"))
      (node (ref "SW5") (pin "A@2") (pinfunction "A_A@2") (pintype "passive"))
      (node (ref "SW6") (pin "A@1") (pinfunction "A_A@1") (pintype "passive"))
      (node (ref "SW6") (pin "A@2") (pinfunction "A_A@2") (pintype "passive"))
      (node (ref "U3") (pin "P$19") (pinfunction "GND_P$19") (pintype "bidirectional"))
      (node (ref "U3") (pin "P$36") (pinfunction "GND_P$36") (pintype "bidirectional"))
      (node (ref "U3") (pin "P$37") (pinfunction "GND_P$37") (pintype "bidirectional"))
      (node (ref "U3") (pin "P$38") (pinfunction "GND_P$38") (pintype "bidirectional"))
      (node (ref "U3") (pin "P$39") (pinfunction "GND_P$39") (pintype "bidirectional"))
      (node (ref "U3") (pin "P$40") (pinfunction "GND_P$40") (pintype "bidirectional"))
      (node (ref "U3") (pin "P$41") (pinfunction "GND_P$41") (pintype "bidirectional"))
      (node (ref "U3") (pin "P$42") (pinfunction "GND_P$42") (pintype "bidirectional"))
      (node (ref "U3") (pin "P$43") (pinfunction "GND_P$43") (pintype "bidirectional"))
      (node (ref "U3") (pin "P$44") (pinfunction "GND_P$44") (pintype "bidirectional"))
      (node (ref "X1") (pin "4") (pinfunction "4_4") (pintype "passive"))
      (node (ref "X2") (pin "6") (pinfunction "6_6") (pintype "bidirectional"))
      (node (ref "X2") (pin "K2") (pinfunction "SW2_K2") (pintype "bidirectional"))
    )
    (net (code "27") (name "GPIO-4") (class "Default")
      (node (ref "J2") (pin "6") (pinfunction "6_6") (pintype "passive"))
      (node (ref "LED1") (pin "A") (pinfunction "A_A") (pintype "passive"))
      (node (ref "U3") (pin "P$29") (pinfunction "GPIO-4_P$29") (pintype "bidirectional"))
    )
    (net (code "28") (name "GPIO-5") (class "Default")
      (node (ref "J2") (pin "7") (pinfunction "7_7") (pintype "passive"))
      (node (ref "U3") (pin "P$28") (pinfunction "GPIO-5_P$28") (pintype "bidirectional"))
    )
    (net (code "29") (name "GPIO-6") (class "Default")
      (node (ref "J2") (pin "8") (pinfunction "8_8") (pintype "passive"))
      (node (ref "LED2") (pin "A") (pinfunction "A_A") (pintype "passive"))
      (node (ref "U3") (pin "P$27") (pinfunction "GPIO-6_P$27") (pintype "bidirectional"))
    )
    (net (code "30") (name "GPIO-7") (class "Default")
      (node (ref "J2") (pin "9") (pinfunction "9_9") (pintype "passive"))
      (node (ref "U3") (pin "P$26") (pinfunction "GPIO-7_P$26") (pintype "bidirectional"))
    )
    (net (code "31") (name "GPIO-8") (class "Default")
      (node (ref "J2") (pin "10") (pinfunction "10_10") (pintype "passive"))
      (node (ref "U3") (pin "P$25") (pinfunction "GPIO-8_P$25") (pintype "bidirectional"))
    )
    (net (code "32") (name "GPIO-9") (class "Default")
      (node (ref "J2") (pin "11") (pinfunction "11_11") (pintype "passive"))
      (node (ref "JP6") (pin "2") (pinfunction "2_2") (pintype "passive"))
      (node (ref "U3") (pin "P$24") (pinfunction "GPIO-9_P$24") (pintype "bidirectional"))
    )
    (net (code "33") (name "GPIO-12") (class "Default")
      (node (ref "J1") (pin "11") (pinfunction "11_11") (pintype "passive"))
      (node (ref "U3") (pin "P$11") (pinfunction "GPIO-12_P$11") (pintype "bidirectional"))
    )
    (net (code "34") (name "GPIO-13") (class "Default")
      (node (ref "J1") (pin "10") (pinfunction "10_10") (pintype "passive"))
      (node (ref "U3") (pin "P$10") (pinfunction "GPIO-13_P$10") (pintype "bidirectional"))
    )
    (net (code "35") (name "LCD_VEE") (class "Default")
      (node (ref "JP1") (pin "5") (pinfunction "5_5") (pintype "passive"))
      (node (ref "R1") (pin "2") (pinfunction "2_2") (pintype "passive"))
    )
    (net (code "36") (name "MISO") (class "Default")
      (node (ref "IC1") (pin "7") (pinfunction "(MISO/PCINT14)PB6_7") (pintype "bidirectional"))
      (node (ref "IC3") (pin "30") (pinfunction "SO_30") (pintype "output"))
      (node (ref "JP3") (pin "1") (pinfunction "1_1") (pintype "passive"))
      (node (ref "R22") (pin "2") (pinfunction "2_2") (pintype "passive"))
      (node (ref "X2") (pin "7") (pinfunction "7_7") (pintype "bidirectional"))
    )
    (net (code "37") (name "MISO1") (class "Default")
      (node (ref "J1") (pin "16") (pinfunction "16_16") (pintype "passive"))
      (node (ref "U3") (pin "P$16") (pinfunction "MISO_P$16") (pintype "bidirectional"))
    )
    (net (code "38") (name "MOSI") (class "Default")
      (node (ref "IC1") (pin "6") (pinfunction "(MOSI/PCINT13)PB5_6") (pintype "bidirectional"))
      (node (ref "IC4") (pin "3") (pinfunction "I_3") (pintype "input"))
      (node (ref "JP3") (pin "4") (pinfunction "4_4") (pintype "passive"))
    )
    (net (code "39") (name "MOSI1") (class "Default")
      (node (ref "J1") (pin "14") (pinfunction "14_14") (pintype "passive"))
      (node (ref "U3") (pin "P$14") (pinfunction "MOSI_P$14") (pintype "bidirectional"))
    )
    (net (code "40") (name "MOSI_3V") (class "Default")
      (node (ref "IC3") (pin "29") (pinfunction "SI_29") (pintype "input"))
      (node (ref "IC4") (pin "2") (pinfunction "O_2") (pintype "output"))
      (node (ref "X2") (pin "3") (pinfunction "3_3") (pintype "bidirectional"))
    )
    (net (code "41") (name "Net-(C14-Pad1)") (class "Default")
      (node (ref "C14") (pin "1") (pinfunction "1_1") (pintype "passive"))
      (node (ref "R3") (pin "1") (pinfunction "1_1") (pintype "passive"))
    )
    (net (code "42") (name "Net-(C15-Pad1)") (class "Default")
      (node (ref "C15") (pin "1") (pinfunction "1_1") (pintype "passive"))
      (node (ref "R4") (pin "1") (pinfunction "1_1") (pintype "passive"))
    )
    (net (code "43") (name "Net-(C16-Pad1)") (class "Default")
      (node (ref "C16") (pin "1") (pinfunction "1_1") (pintype "passive"))
      (node (ref "R5") (pin "1") (pinfunction "1_1") (pintype "passive"))
    )
    (net (code "44") (name "Net-(IC1-XTAL1)") (class "Default")
      (node (ref "C21") (pin "1") (pinfunction "1_1") (pintype "passive"))
      (node (ref "IC1") (pin "13") (pinfunction "XTAL1_13") (pintype "input"))
      (node (ref "Q2") (pin "2") (pinfunction "2_2") (pintype "passive"))
    )
    (net (code "45") (name "Net-(IC1-XTAL2)") (class "Default")
      (node (ref "C22") (pin "1") (pinfunction "1_1") (pintype "passive"))
      (node (ref "IC1") (pin "12") (pinfunction "XTAL2_12") (pintype "output"))
      (node (ref "Q2") (pin "1") (pinfunction "1_1") (pintype "passive"))
    )
    (net (code "46") (name "Net-(IC2-3V3OUT)") (class "Default")
      (node (ref "C18") (pin "2") (pinfunction "2_2") (pintype "passive"))
      (node (ref "IC2") (pin "17") (pinfunction "3V3OUT_17") (pintype "output"))
    )
    (net (code "47") (name "Net-(IC2-USBDM)") (class "Default")
      (node (ref "IC2") (pin "16") (pinfunction "USBDM_16") (pintype "bidirectional"))
      (node (ref "X1") (pin "2") (pinfunction "2_2") (pintype "passive"))
    )
    (net (code "48") (name "Net-(IC2-USBDP)") (class "Default")
      (node (ref "IC2") (pin "15") (pinfunction "USBDP_15") (pintype "bidirectional"))
      (node (ref "X1") (pin "3") (pinfunction "3_3") (pintype "passive"))
    )
    (net (code "49") (name "Net-(IC2-~{RESET})") (class "Default")
      (node (ref "IC2") (pin "19") (pinfunction "~{RESET}_19") (pintype "input"))
      (node (ref "R10") (pin "2") (pinfunction "2_2") (pintype "passive"))
      (node (ref "R9") (pin "2") (pinfunction "2_2") (pintype "passive"))
    )
    (net (code "50") (name "Net-(IC3-GBUF)") (class "Default")
      (node (ref "IC3") (pin "42") (pinfunction "GBUF_42") (pintype "passive"))
      (node (ref "R5") (pin "2") (pinfunction "2_2") (pintype "passive"))
      (node (ref "X3") (pin "1") (pinfunction "1_1") (pintype "passive"))
    )
    (net (code "51") (name "Net-(IC3-GPIO0)") (class "Default")
      (node (ref "IC3") (pin "33") (pinfunction "GPIO0_33") (pintype "bidirectional"))
      (node (ref "IC3") (pin "34") (pinfunction "GPIO1_34") (pintype "bidirectional"))
      (node (ref "IC3") (pin "36") (pinfunction "GPIO4_36") (pintype "bidirectional"))
      (node (ref "R15") (pin "2") (pinfunction "2_2") (pintype "passive"))
    )
    (net (code "52") (name "Net-(IC3-GPIO2)") (class "Default")
      (node (ref "IC3") (pin "10") (pinfunction "GPIO3_10") (pintype "bidirectional"))
      (node (ref "IC3") (pin "11") (pinfunction "GPIO6_11") (pintype "bidirectional"))
      (node (ref "IC3") (pin "12") (pinfunction "GPIO7_12") (pintype "bidirectional"))
      (node (ref "IC3") (pin "9") (pinfunction "GPIO2_9") (pintype "bidirectional"))
      (node (ref "R8") (pin "2") (pinfunction "2_2") (pintype "passive"))
    )
    (net (code "53") (name "Net-(IC3-GPIO5)") (class "Default")
      (node (ref "IC3") (pin "25") (pinfunction "GPIO5_25") (pintype "bidirectional"))
      (node (ref "R17") (pin "2") (pinfunction "2_2") (pintype "passive"))
    )
    (net (code "54") (name "Net-(IC3-LEFT)") (class "Default")
      (node (ref "IC3") (pin "46") (pinfunction "LEFT_46") (pintype "passive"))
      (node (ref "R3") (pin "2") (pinfunction "2_2") (pintype "passive"))
      (node (ref "X3") (pin "3") (pinfunction "3_3") (pintype "passive"))
    )
    (net (code "55") (name "Net-(IC3-RCAP)") (class "Default")
      (node (ref "C13") (pin "1") (pinfunction "1_1") (pintype "passive"))
      (node (ref "IC3") (pin "44") (pinfunction "RCAP_44") (pintype "passive"))
    )
    (net (code "56") (name "Net-(IC3-RIGHT)") (class "Default")
      (node (ref "IC3") (pin "39") (pinfunction "RIGHT_39") (pintype "passive"))
      (node (ref "R4") (pin "2") (pinfunction "2_2") (pintype "passive"))
      (node (ref "X3") (pin "2") (pinfunction "2_2") (pintype "passive"))
    )
    (net (code "57") (name "Net-(IC3-XTALI)") (class "Default")
      (node (ref "C12") (pin "1") (pinfunction "1_1") (pintype "passive"))
      (node (ref "IC3") (pin "18") (pinfunction "XTALI_18") (pintype "passive"))
      (node (ref "Q1") (pin "1") (pinfunction "1_1") (pintype "passive"))
      (node (ref "R2") (pin "1") (pinfunction "1_1") (pintype "passive"))
    )
    (net (code "58") (name "Net-(IC3-XTALO)") (class "Default")
      (node (ref "C11") (pin "1") (pinfunction "1_1") (pintype "passive"))
      (node (ref "IC3") (pin "17") (pinfunction "XTALO_17") (pintype "passive"))
      (node (ref "Q1") (pin "2") (pinfunction "2_2") (pintype "passive"))
      (node (ref "R2") (pin "2") (pinfunction "2_2") (pintype "passive"))
    )
    (net (code "59") (name "Net-(IC3-~{RESET})") (class "Default")
      (node (ref "IC3") (pin "3") (pinfunction "~{RESET}_3") (pintype "input"))
      (node (ref "R7") (pin "2") (pinfunction "2_2") (pintype "passive"))
    )
    (net (code "60") (name "Net-(JP1-Pad4)") (class "Default")
      (node (ref "JP1") (pin "4") (pinfunction "4_4") (pintype "passive"))
      (node (ref "R1") (pin "3") (pinfunction "3_3") (pintype "passive"))
    )
    (net (code "61") (name "Net-(JP1-Pad10)") (class "Default")
      (node (ref "JP1") (pin "10") (pinfunction "10_10") (pintype "passive"))
      (node (ref "R16") (pin "2") (pinfunction "2_2") (pintype "passive"))
    )
    (net (code "62") (name "Net-(LED1-PadC)") (class "Default")
      (node (ref "LED1") (pin "C") (pinfunction "C_C") (pintype "passive"))
      (node (ref "R23") (pin "1") (pinfunction "1_1") (pintype "passive"))
    )
    (net (code "63") (name "Net-(LED2-PadC)") (class "Default")
      (node (ref "LED2") (pin "C") (pinfunction "C_C") (pintype "passive"))
      (node (ref "R24") (pin "1") (pinfunction "1_1") (pintype "passive"))
    )
    (net (code "64") (name "Net-(R9-Pad1)") (class "Default")
      (node (ref "R9") (pin "1") (pinfunction "1_1") (pintype "passive"))
      (node (ref "X1") (pin "1") (pinfunction "1_1") (pintype "passive"))
    )
    (net (code "65") (name "Net-(U1-ADJ)") (class "Default")
      (node (ref "R20") (pin "1") (pinfunction "1_1") (pintype "passive"))
      (node (ref "R21") (pin "1") (pinfunction "1_1") (pintype "passive"))
      (node (ref "U1") (pin "1") (pinfunction "ADJ_1") (pintype "passive"))
    )
    (net (code "66") (name "Net-(U2-ADJ)") (class "Default")
      (node (ref "R18") (pin "1") (pinfunction "1_1") (pintype "passive"))
      (node (ref "R19") (pin "1") (pinfunction "1_1") (pintype "passive"))
      (node (ref "U2") (pin "1") (pinfunction "ADJ_1") (pintype "passive"))
    )
    (net (code "67") (name "RESET") (class "Default")
      (node (ref "J1") (pin "5") (pinfunction "5_5") (pintype "passive"))
      (node (ref "U3") (pin "P$5") (pinfunction "RESET_P$5") (pintype "bidirectional"))
    )
    (net (code "68") (name "RX") (class "Default")
      (node (ref "J1") (pin "12") (pinfunction "12_12") (pintype "passive"))
      (node (ref "U3") (pin "P$12") (pinfunction "RX_P$12") (pintype "bidirectional"))
    )
    (net (code "69") (name "SCK") (class "Default")
      (node (ref "IC1") (pin "8") (pinfunction "(SCK/PCINT15)PB7_8") (pintype "bidirectional"))
      (node (ref "IC4") (pin "5") (pinfunction "I_5") (pintype "input"))
      (node (ref "JP3") (pin "3") (pinfunction "3_3") (pintype "passive"))
    )
    (net (code "70") (name "SCK_3V") (class "Default")
      (node (ref "IC3") (pin "28") (pinfunction "SCLK_28") (pintype "input"))
      (node (ref "IC4") (pin "4") (pinfunction "O_4") (pintype "output"))
      (node (ref "X2") (pin "5") (pinfunction "5_5") (pintype "bidirectional"))
    )
    (net (code "71") (name "SD_~{CS}") (class "Default")
      (node (ref "IC4") (pin "6") (pinfunction "O_6") (pintype "output"))
      (node (ref "X2") (pin "2") (pinfunction "2_2") (pintype "bidirectional"))
    )
    (net (code "72") (name "SD_~{CS}_I") (class "Default")
      (node (ref "IC1") (pin "5") (pinfunction "(OC0B/~{SS}/PCINT12)PB4_5") (pintype "bidirectional"))
      (node (ref "IC4") (pin "7") (pinfunction "I_7") (pintype "input"))
      (node (ref "R14") (pin "2") (pinfunction "2_2") (pintype "passive"))
    )
    (net (code "73") (name "SEN0") (class "Default")
      (node (ref "J2") (pin "1") (pinfunction "1_1") (pintype "passive"))
      (node (ref "U3") (pin "P$34") (pinfunction "SEN0_P$34") (pintype "bidirectional"))
    )
    (net (code "74") (name "SEN1") (class "Default")
      (node (ref "J2") (pin "5") (pinfunction "5_5") (pintype "passive"))
      (node (ref "U3") (pin "P$30") (pinfunction "SEN1_P$30") (pintype "bidirectional"))
    )
    (net (code "75") (name "SEN2") (class "Default")
      (node (ref "J2") (pin "4") (pinfunction "4_4") (pintype "passive"))
      (node (ref "U3") (pin "P$31") (pinfunction "SEN2_P$31") (pintype "bidirectional"))
    )
    (net (code "76") (name "SEN3") (class "Default")
      (node (ref "J2") (pin "3") (pinfunction "3_3") (pintype "passive"))
      (node (ref "U3") (pin "P$32") (pinfunction "SEN3_P$32") (pintype "bidirectional"))
    )
    (net (code "77") (name "SEN4") (class "Default")
      (node (ref "J1") (pin "2") (pinfunction "2_2") (pintype "passive"))
      (node (ref "U3") (pin "P$2") (pinfunction "SEN4_P$2") (pintype "bidirectional"))
    )
    (net (code "78") (name "SEN5") (class "Default")
      (node (ref "J1") (pin "3") (pinfunction "3_3") (pintype "passive"))
      (node (ref "U3") (pin "P$3") (pinfunction "SEN5_P$3") (pintype "bidirectional"))
    )
    (net (code "79") (name "SEN6") (class "Default")
      (node (ref "J1") (pin "1") (pinfunction "1_1") (pintype "passive"))
      (node (ref "U3") (pin "P$1") (pinfunction "SEN6_P$1") (pintype "bidirectional"))
    )
    (net (code "80") (name "SEN7") (class "Default")
      (node (ref "J1") (pin "4") (pinfunction "4_4") (pintype "passive"))
      (node (ref "U3") (pin "P$4") (pinfunction "SEN7_P$4") (pintype "bidirectional"))
    )
    (net (code "81") (name "SENSE-PWR") (class "Default")
      (node (ref "J2") (pin "2") (pinfunction "2_2") (pintype "passive"))
      (node (ref "U3") (pin "P$33") (pinfunction "SENSE-PWR_P$33") (pintype "bidirectional"))
    )
    (net (code "82") (name "SW_0") (class "Default")
      (node (ref "IC1") (pin "40") (pinfunction "(ADC0/PCINT0)PA0_40") (pintype "bidirectional"))
      (node (ref "SV1") (pin "1") (pinfunction "1_1") (pintype "passive"))
    )
    (net (code "83") (name "SW_1") (class "Default")
      (node (ref "IC1") (pin "39") (pinfunction "(ADC1/PCINT1)PA1_39") (pintype "bidirectional"))
      (node (ref "SV1") (pin "2") (pinfunction "2_2") (pintype "passive"))
    )
    (net (code "84") (name "SW_2") (class "Default")
      (node (ref "IC1") (pin "38") (pinfunction "(ADC2/PCINT2)PA2_38") (pintype "bidirectional"))
      (node (ref "SV1") (pin "3") (pinfunction "3_3") (pintype "passive"))
    )
    (net (code "85") (name "SW_3") (class "Default")
      (node (ref "IC1") (pin "37") (pinfunction "(ADC3/PCINT3)PA3_37") (pintype "bidirectional"))
      (node (ref "SV1") (pin "4") (pinfunction "4_4") (pintype "passive"))
    )
    (net (code "86") (name "SW_4") (class "Default")
      (node (ref "IC1") (pin "36") (pinfunction "(ADC4/PCINT4)PA4_36") (pintype "bidirectional"))
      (node (ref "SV1") (pin "5") (pinfunction "5_5") (pintype "passive"))
    )
    (net (code "87") (name "SW_5") (class "Default")
      (node (ref "IC1") (pin "35") (pinfunction "(ADC5/PCINT5)PA5_35") (pintype "bidirectional"))
      (node (ref "SV1") (pin "6") (pinfunction "6_6") (pintype "passive"))
    )
    (net (code "88") (name "SW_6") (class "Default")
      (node (ref "IC1") (pin "34") (pinfunction "(ADC6/PCINT6)PA6_34") (pintype "bidirectional"))
      (node (ref "SV1") (pin "7") (pinfunction "7_7") (pintype "passive"))
    )
    (net (code "89") (name "SW_7") (class "Default")
      (node (ref "IC1") (pin "33") (pinfunction "(ADC7/PCINT7)PA7_33") (pintype "bidirectional"))
      (node (ref "SV1") (pin "8") (pinfunction "8_8") (pintype "passive"))
    )
    (net (code "90") (name "SW_A") (class "Default")
      (node (ref "SV2") (pin "7") (pinfunction "7_7") (pintype "passive"))
      (node (ref "SW2") (pin "B@1") (pinfunction "B_B@1") (pintype "passive"))
      (node (ref "SW2") (pin "B@2") (pinfunction "B_B@2") (pintype "passive"))
    )
    (net (code "91") (name "SW_B") (class "Default")
      (node (ref "SV2") (pin "1") (pinfunction "1_1") (pintype "passive"))
      (node (ref "SW3") (pin "B@1") (pinfunction "B_B@1") (pintype "passive"))
      (node (ref "SW3") (pin "B@2") (pinfunction "B_B@2") (pintype "passive"))
    )
    (net (code "92") (name "SW_C") (class "Default")
      (node (ref "SV2") (pin "2") (pinfunction "2_2") (pintype "passive"))
      (node (ref "SW4") (pin "B@1") (pinfunction "B_B@1") (pintype "passive"))
      (node (ref "SW4") (pin "B@2") (pinfunction "B_B@2") (pintype "passive"))
    )
    (net (code "93") (name "SW_D") (class "Default")
      (node (ref "SV2") (pin "8") (pinfunction "8_8") (pintype "passive"))
      (node (ref "SW5") (pin "B@1") (pinfunction "B_B@1") (pintype "passive"))
      (node (ref "SW5") (pin "B@2") (pinfunction "B_B@2") (pintype "passive"))
    )
    (net (code "94") (name "SW_E") (class "Default")
      (node (ref "SV2") (pin "3") (pinfunction "3_3") (pintype "passive"))
      (node (ref "SW6") (pin "B@1") (pinfunction "B_B@1") (pintype "passive"))
      (node (ref "SW6") (pin "B@2") (pinfunction "B_B@2") (pintype "passive"))
    )
    (net (code "95") (name "SW_F") (class "Default")
      (node (ref "SV2") (pin "5") (pinfunction "5_5") (pintype "passive"))
      (node (ref "SW1") (pin "A") (pinfunction "A_A") (pintype "passive"))
    )
    (net (code "96") (name "SW_G") (class "Default")
      (node (ref "SV2") (pin "4") (pinfunction "4_4") (pintype "passive"))
      (node (ref "SW1") (pin "B") (pinfunction "B_B") (pintype "passive"))
    )
    (net (code "97") (name "SW_H") (class "Default")
      (node (ref "SV2") (pin "6") (pinfunction "6_6") (pintype "passive"))
      (node (ref "SW1") (pin "P1") (pinfunction "1_P1") (pintype "passive"))
    )
    (net (code "98") (name "S_CAP") (class "Default")
      (node (ref "J1") (pin "8") (pinfunction "8_8") (pintype "passive"))
      (node (ref "U3") (pin "P$8") (pinfunction "S_CAP_P$8") (pintype "bidirectional"))
    )
    (net (code "99") (name "TX") (class "Default")
      (node (ref "J1") (pin "13") (pinfunction "13_13") (pintype "passive"))
      (node (ref "U3") (pin "P$13") (pinfunction "TX_P$13") (pintype "bidirectional"))
    )
    (net (code "100") (name "VDD-BATT") (class "Default")
      (node (ref "J2") (pin "15") (pinfunction "15_15") (pintype "passive"))
      (node (ref "JP5") (pin "1") (pinfunction "1_1") (pintype "passive"))
      (node (ref "U3") (pin "P$20") (pinfunction "VDD-BATT_P$20") (pintype "bidirectional"))
    )
    (net (code "101") (name "VDD-IN") (class "Default")
      (node (ref "J2") (pin "14") (pinfunction "14_14") (pintype "passive"))
      (node (ref "JP5") (pin "2") (pinfunction "2_2") (pintype "passive"))
      (node (ref "JP6") (pin "1") (pinfunction "1_1") (pintype "passive"))
      (node (ref "U3") (pin "P$21") (pinfunction "VDD-IN_P$21") (pintype "bidirectional"))
    )
    (net (code "102") (name "VS_RXD") (class "Default")
      (node (ref "IC3") (pin "26") (pinfunction "RX_26") (pintype "input"))
      (node (ref "JP2") (pin "1") (pinfunction "1_1") (pintype "passive"))
      (node (ref "R6") (pin "1") (pinfunction "1_1") (pintype "passive"))
    )
    (net (code "103") (name "VS_TXD") (class "Default")
      (node (ref "IC3") (pin "27") (pinfunction "TX_27") (pintype "output"))
      (node (ref "JP2") (pin "2") (pinfunction "2_2") (pintype "passive"))
    )
    (net (code "104") (name "VS_~{CS}") (class "Default")
      (node (ref "IC3") (pin "23") (pinfunction "~{CS}_23") (pintype "input"))
      (node (ref "IC4") (pin "10") (pinfunction "O_10") (pintype "output"))
    )
    (net (code "105") (name "VS_~{CS}_I") (class "Default")
      (node (ref "IC1") (pin "4") (pinfunction "(OC0A/AIN1/PCINT11)PB3_4") (pintype "bidirectional"))
      (node (ref "IC4") (pin "9") (pinfunction "I_9") (pintype "input"))
      (node (ref "R13") (pin "2") (pinfunction "2_2") (pintype "passive"))
    )
    (net (code "106") (name "VS_~{DCS}") (class "Default")
      (node (ref "IC3") (pin "13") (pinfunction "~{DCS}_13") (pintype "input"))
      (node (ref "IC4") (pin "12") (pinfunction "O_12") (pintype "output"))
    )
    (net (code "107") (name "VS_~{DREQ}") (class "Default")
      (node (ref "IC1") (pin "2") (pinfunction "(CLKO/T1/PCINT9)PB1_2") (pintype "bidirectional"))
      (node (ref "IC3") (pin "8") (pinfunction "~{DREQ}_8") (pintype "input"))
    )
    (net (code "108") (name "unconnected-(IC1-(OC2A{slash}PCINT31)PD7-Pad21)") (class "Default")
      (node (ref "IC1") (pin "21") (pinfunction "(OC2A/PCINT31)PD7_21") (pintype "bidirectional"))
    )
    (net (code "109") (name "unconnected-(IC1-(OC2B{slash}ICP{slash}PCINT30)PD6-Pad20)") (class "Default")
      (node (ref "IC1") (pin "20") (pinfunction "(OC2B/ICP/PCINT30)PD6_20") (pintype "bidirectional"))
    )
    (net (code "110") (name "unconnected-(IC2-CBUS0-Pad23)") (class "Default")
      (node (ref "IC2") (pin "23") (pinfunction "CBUS0_23") (pintype "bidirectional"))
    )
    (net (code "111") (name "unconnected-(IC2-CBUS1-Pad22)") (class "Default")
      (node (ref "IC2") (pin "22") (pinfunction "CBUS1_22") (pintype "bidirectional"))
    )
    (net (code "112") (name "unconnected-(IC2-CBUS2-Pad13)") (class "Default")
      (node (ref "IC2") (pin "13") (pinfunction "CBUS2_13") (pintype "bidirectional"))
    )
    (net (code "113") (name "unconnected-(IC2-CBUS3-Pad14)") (class "Default")
      (node (ref "IC2") (pin "14") (pinfunction "CBUS3_14") (pintype "bidirectional"))
    )
    (net (code "114") (name "unconnected-(IC2-CBUS4-Pad12)") (class "Default")
      (node (ref "IC2") (pin "12") (pinfunction "CBUS4_12") (pintype "bidirectional"))
    )
    (net (code "115") (name "unconnected-(IC2-OSCI-Pad27)") (class "Default")
      (node (ref "IC2") (pin "27") (pinfunction "OSCI_27") (pintype "input"))
    )
    (net (code "116") (name "unconnected-(IC2-OSCO-Pad28)") (class "Default")
      (node (ref "IC2") (pin "28") (pinfunction "OSCO_28") (pintype "output"))
    )
    (net (code "117") (name "unconnected-(IC2-~{CTS}-Pad11)") (class "Default")
      (node (ref "IC2") (pin "11") (pinfunction "~{CTS}_11") (pintype "input"))
    )
    (net (code "118") (name "unconnected-(IC2-~{DCD}-Pad10)") (class "Default")
      (node (ref "IC2") (pin "10") (pinfunction "~{DCD}_10") (pintype "input"))
    )
    (net (code "119") (name "unconnected-(IC2-~{DSR}-Pad9)") (class "Default")
      (node (ref "IC2") (pin "9") (pinfunction "~{DSR}_9") (pintype "input"))
    )
    (net (code "120") (name "unconnected-(IC2-~{DTR}-Pad2)") (class "Default")
      (node (ref "IC2") (pin "2") (pinfunction "~{DTR}_2") (pintype "output"))
    )
    (net (code "121") (name "unconnected-(IC2-~{RI}-Pad6)") (class "Default")
      (node (ref "IC2") (pin "6") (pinfunction "~{RI}_6") (pintype "input"))
    )
    (net (code "122") (name "unconnected-(IC2-~{RTS}-Pad3)") (class "Default")
      (node (ref "IC2") (pin "3") (pinfunction "~{RTS}_3") (pintype "output"))
    )
    (net (code "123") (name "unconnected-(IC3-LINE2-Pad48)") (class "Default")
      (node (ref "IC3") (pin "48") (pinfunction "LINE2_48") (pintype "passive"))
    )
    (net (code "124") (name "unconnected-(IC3-MIC+{slash}LINE1-Pad1)") (class "Default")
      (node (ref "IC3") (pin "1") (pinfunction "MIC+/LINE1_1") (pintype "passive"))
    )
    (net (code "125") (name "unconnected-(IC3-MIC--Pad2)") (class "Default")
      (node (ref "IC3") (pin "2") (pinfunction "MIC-_2") (pintype "passive"))
    )
    (net (code "126") (name "unconnected-(IC3-VCO-Pad15)") (class "Default")
      (node (ref "IC3") (pin "15") (pinfunction "VCO_15") (pintype "output"))
    )
    (net (code "127") (name "unconnected-(IC4F-I-Pad14)") (class "Default")
      (node (ref "IC4") (pin "14") (pinfunction "I_14") (pintype "input"))
    )
    (net (code "128") (name "unconnected-(IC4F-O-Pad15)") (class "Default")
      (node (ref "IC4") (pin "15") (pinfunction "O_15") (pintype "output"))
    )
    (net (code "129") (name "unconnected-(JP1-Pad20)") (class "Default")
      (node (ref "JP1") (pin "20") (pinfunction "20_20") (pintype "passive"))
    )
    (net (code "130") (name "unconnected-(X1-Pad5)") (class "Default")
      (node (ref "X1") (pin "5") (pinfunction "5_5") (pintype "passive"))
    )
    (net (code "131") (name "unconnected-(X2-Pad1)") (class "Default")
      (node (ref "X2") (pin "1") (pinfunction "1_1") (pintype "bidirectional"))
    )
    (net (code "132") (name "unconnected-(X2-Pad8)") (class "Default")
      (node (ref "X2") (pin "8") (pinfunction "8_8") (pintype "bidirectional"))
    )
    (net (code "133") (name "unconnected-(X3-Pad4)") (class "Default")
      (node (ref "X3") (pin "4") (pinfunction "4_4") (pintype "passive"))
    )
    (net (code "134") (name "unconnected-(X3-Pad5)") (class "Default")
      (node (ref "X3") (pin "5") (pinfunction "5_5") (pintype "passive"))
    )
    (net (code "135") (name "~{CE}") (class "Default")
      (node (ref "IC1") (pin "17") (pinfunction "(TXD1/INT1/PCINT27)PD3_17") (pintype "bidirectional"))
      (node (ref "JP1") (pin "8") (pinfunction "8_8") (pintype "passive"))
    )
    (net (code "136") (name "~{RD}") (class "Default")
      (node (ref "IC1") (pin "18") (pinfunction "(XCK1/OC1B/PCINT28)PD4_18") (pintype "bidirectional"))
      (node (ref "JP1") (pin "7") (pinfunction "7_7") (pintype "passive"))
    )
    (net (code "137") (name "~{RESET}") (class "Default")
      (node (ref "C26") (pin "1") (pinfunction "1_1") (pintype "passive"))
      (node (ref "IC1") (pin "9") (pinfunction "~{RESET}_9") (pintype "input"))
      (node (ref "JP1") (pin "11") (pinfunction "11_11") (pintype "passive"))
      (node (ref "JP3") (pin "5") (pinfunction "5_5") (pintype "passive"))
      (node (ref "R11") (pin "1") (pinfunction "1_1") (pintype "passive"))
    )
    (net (code "138") (name "~{WR}") (class "Default")
      (node (ref "IC1") (pin "16") (pinfunction "(RXD1/INT0/PCINT26)PD2_16") (pintype "bidirectional"))
      (node (ref "JP1") (pin "6") (pinfunction "6_6") (pintype "passive"))
    )
  )
)
